# LARIX_V5_1.net
KiCad netlist of a schematic drawn in EAGLE
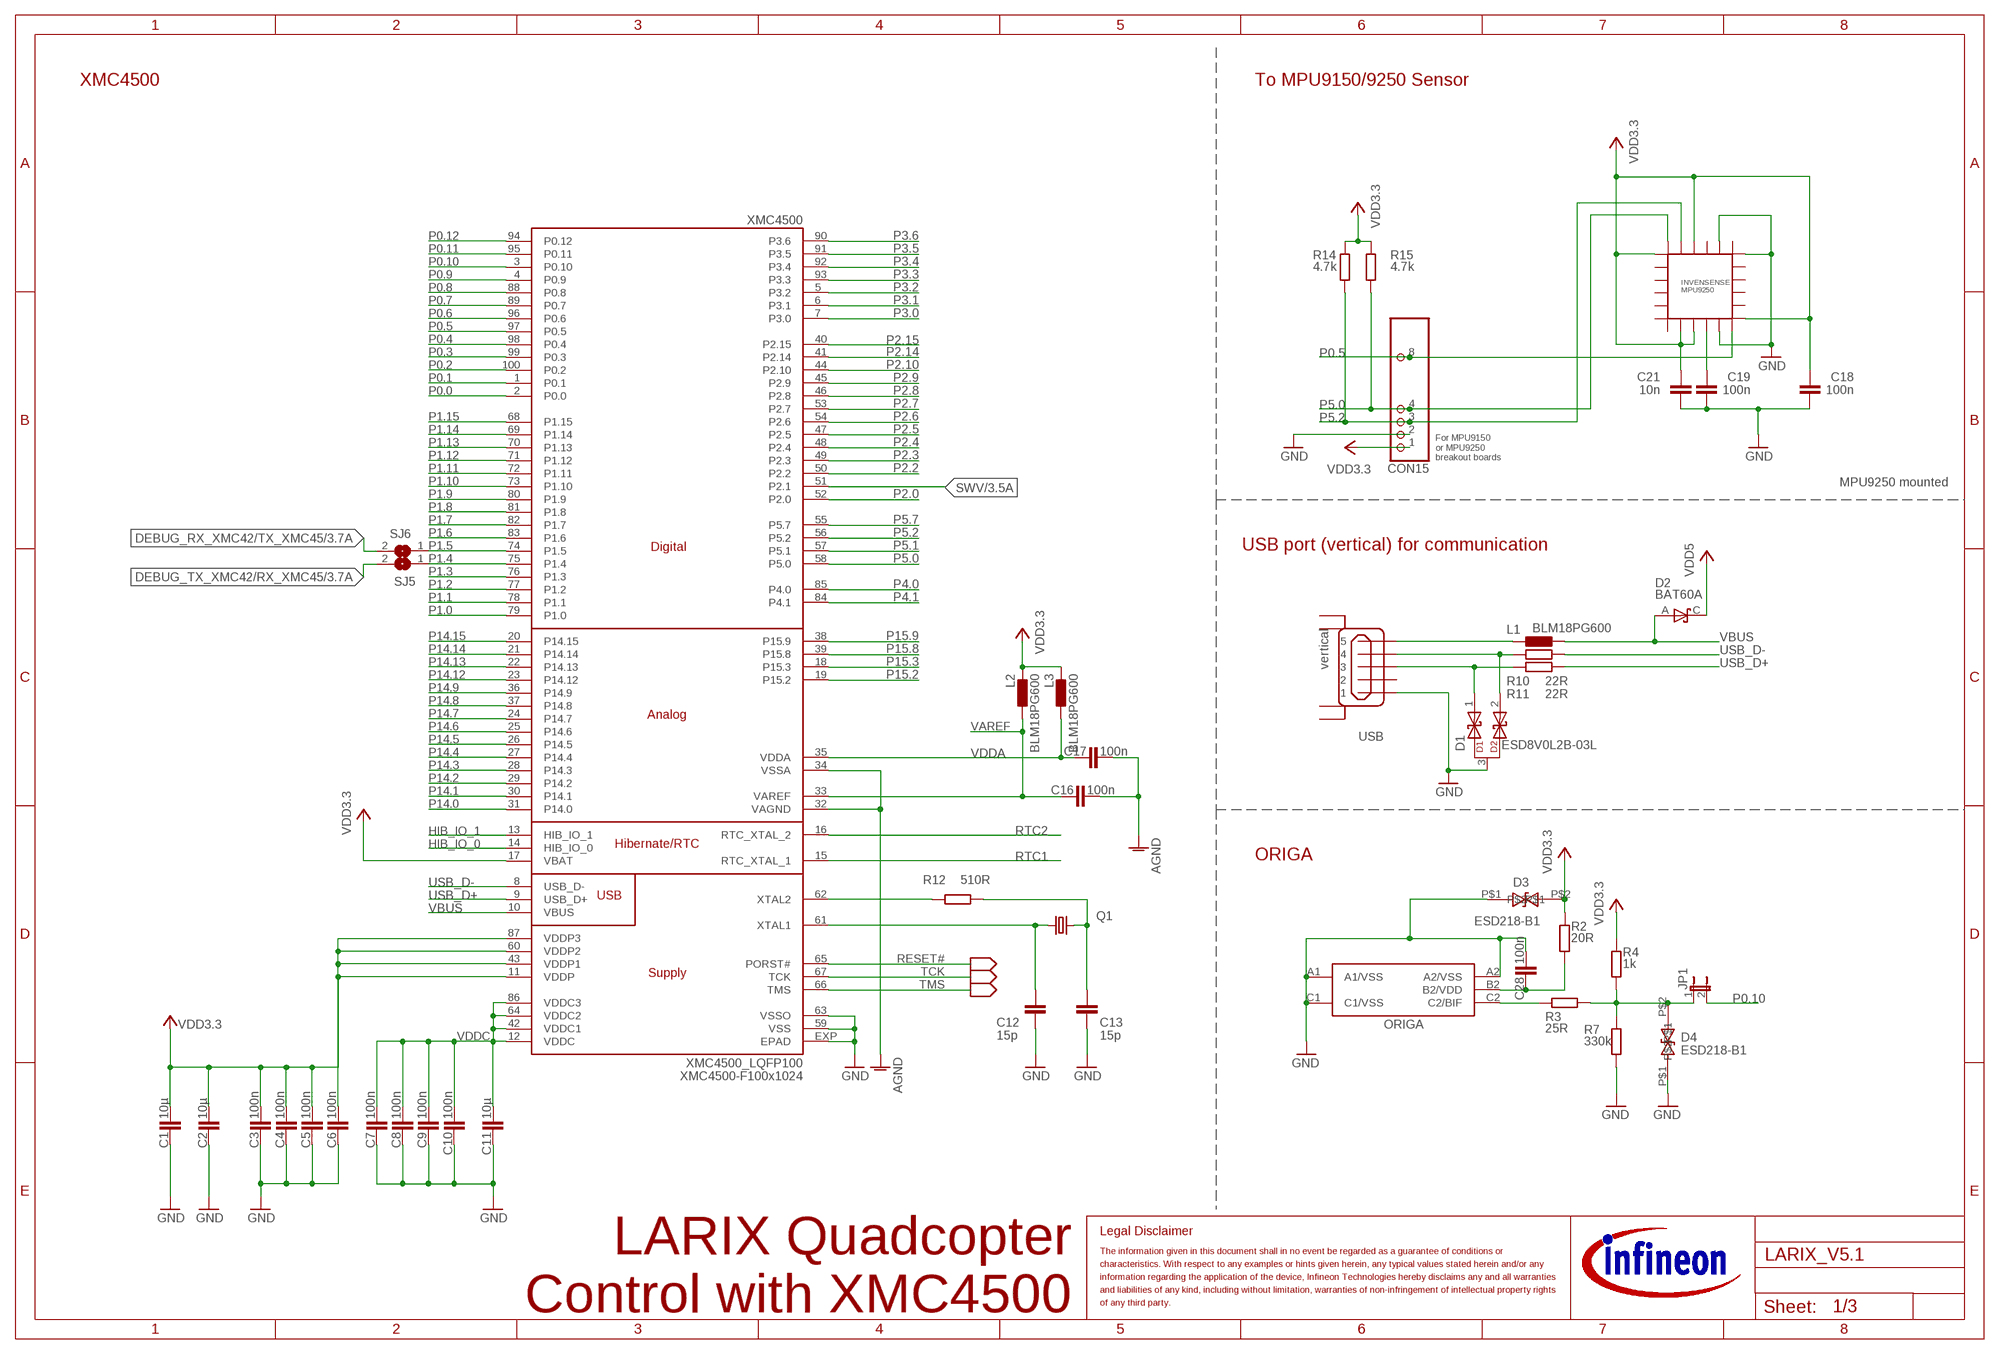
[diagram p0: schematic, sheet 1]
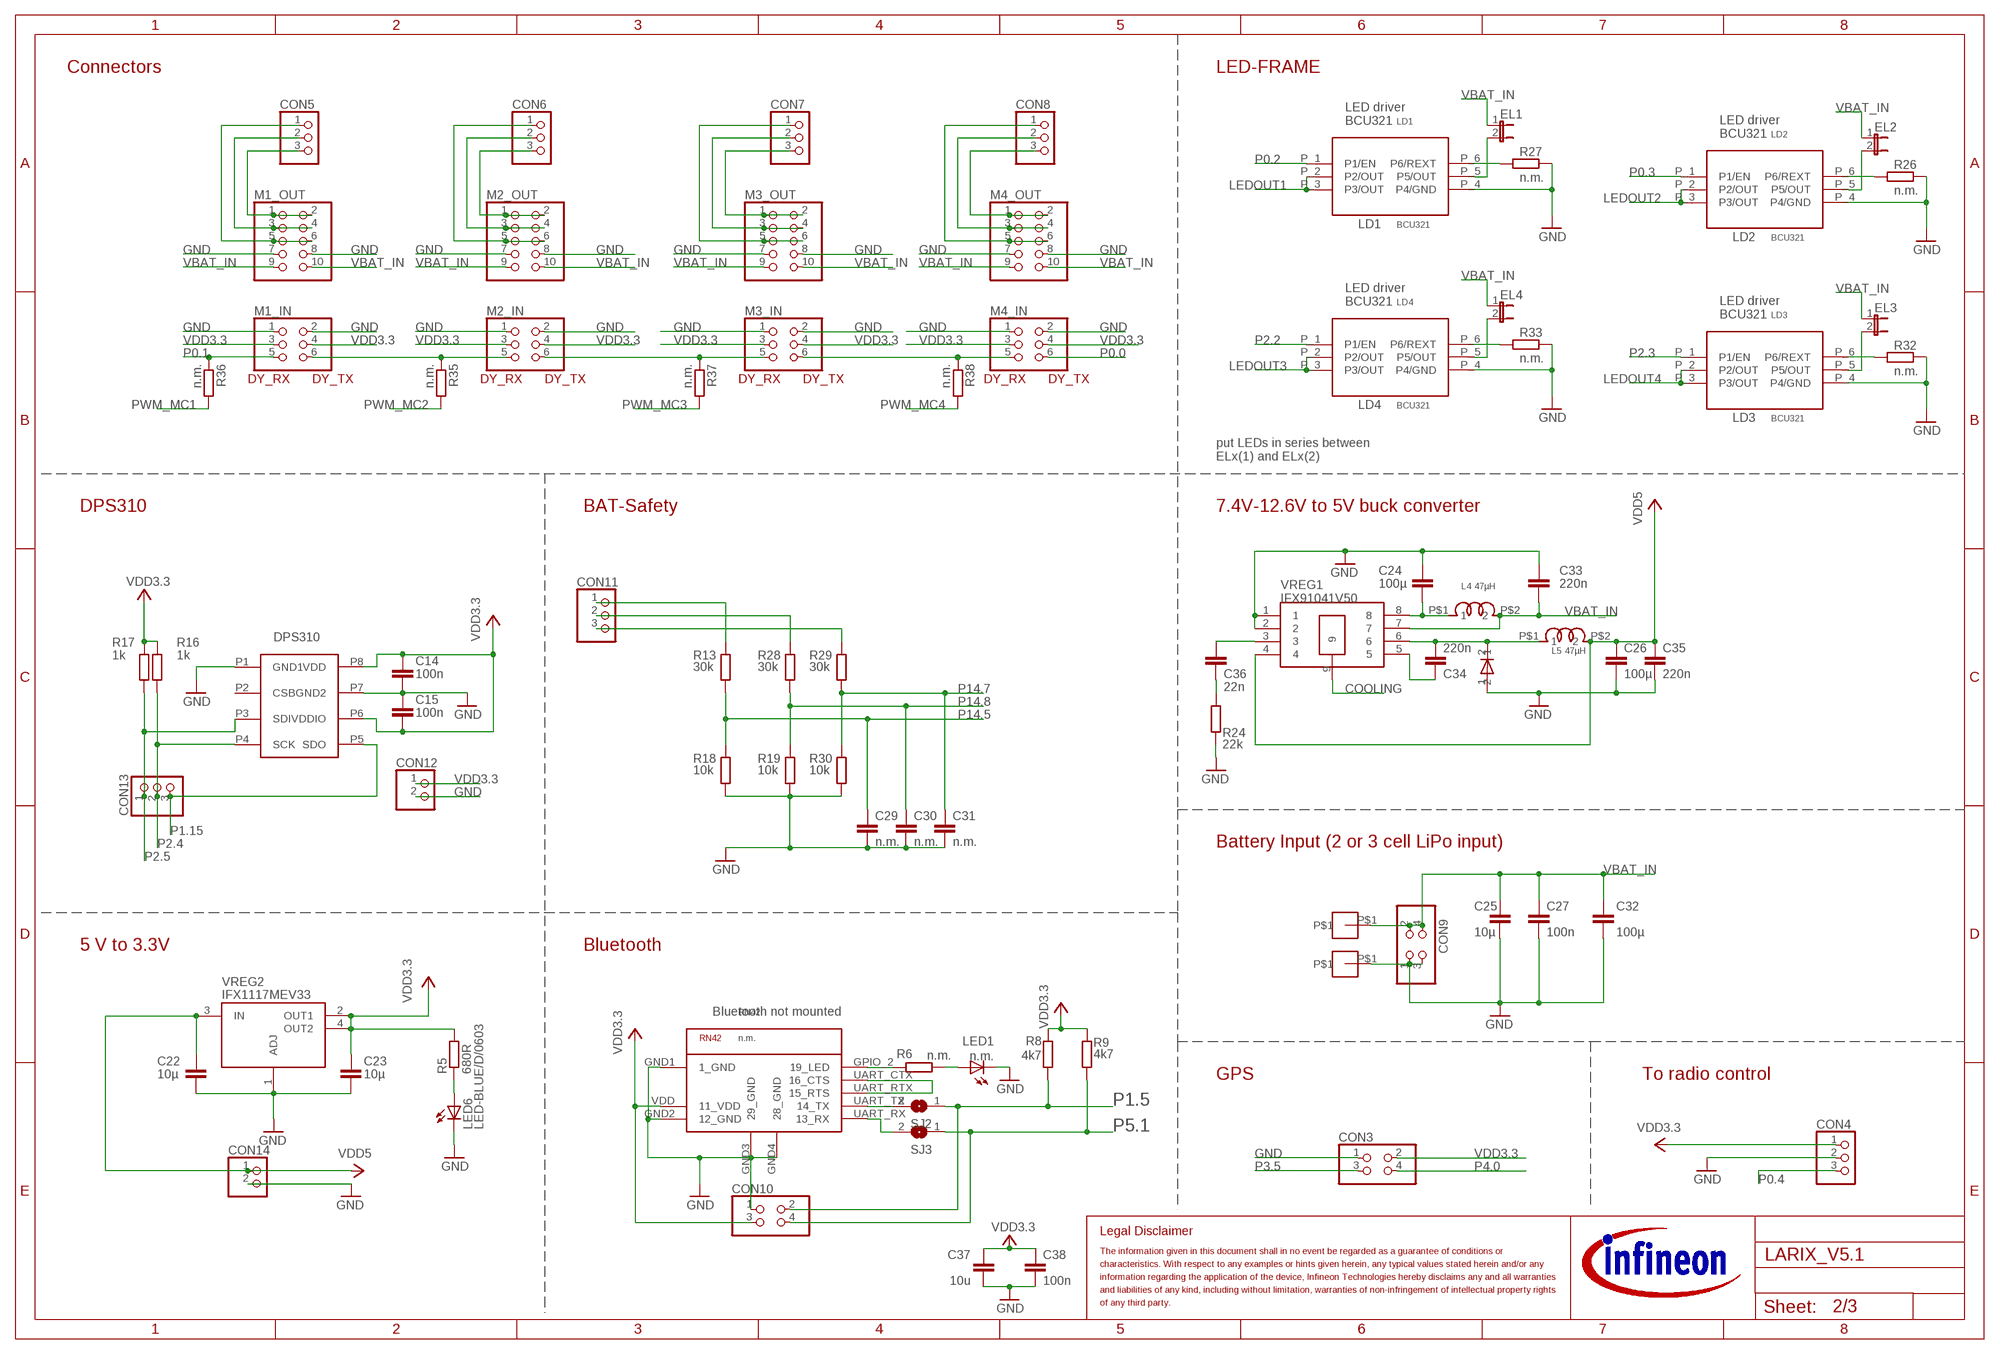
[diagram p1: schematic, sheet 2]
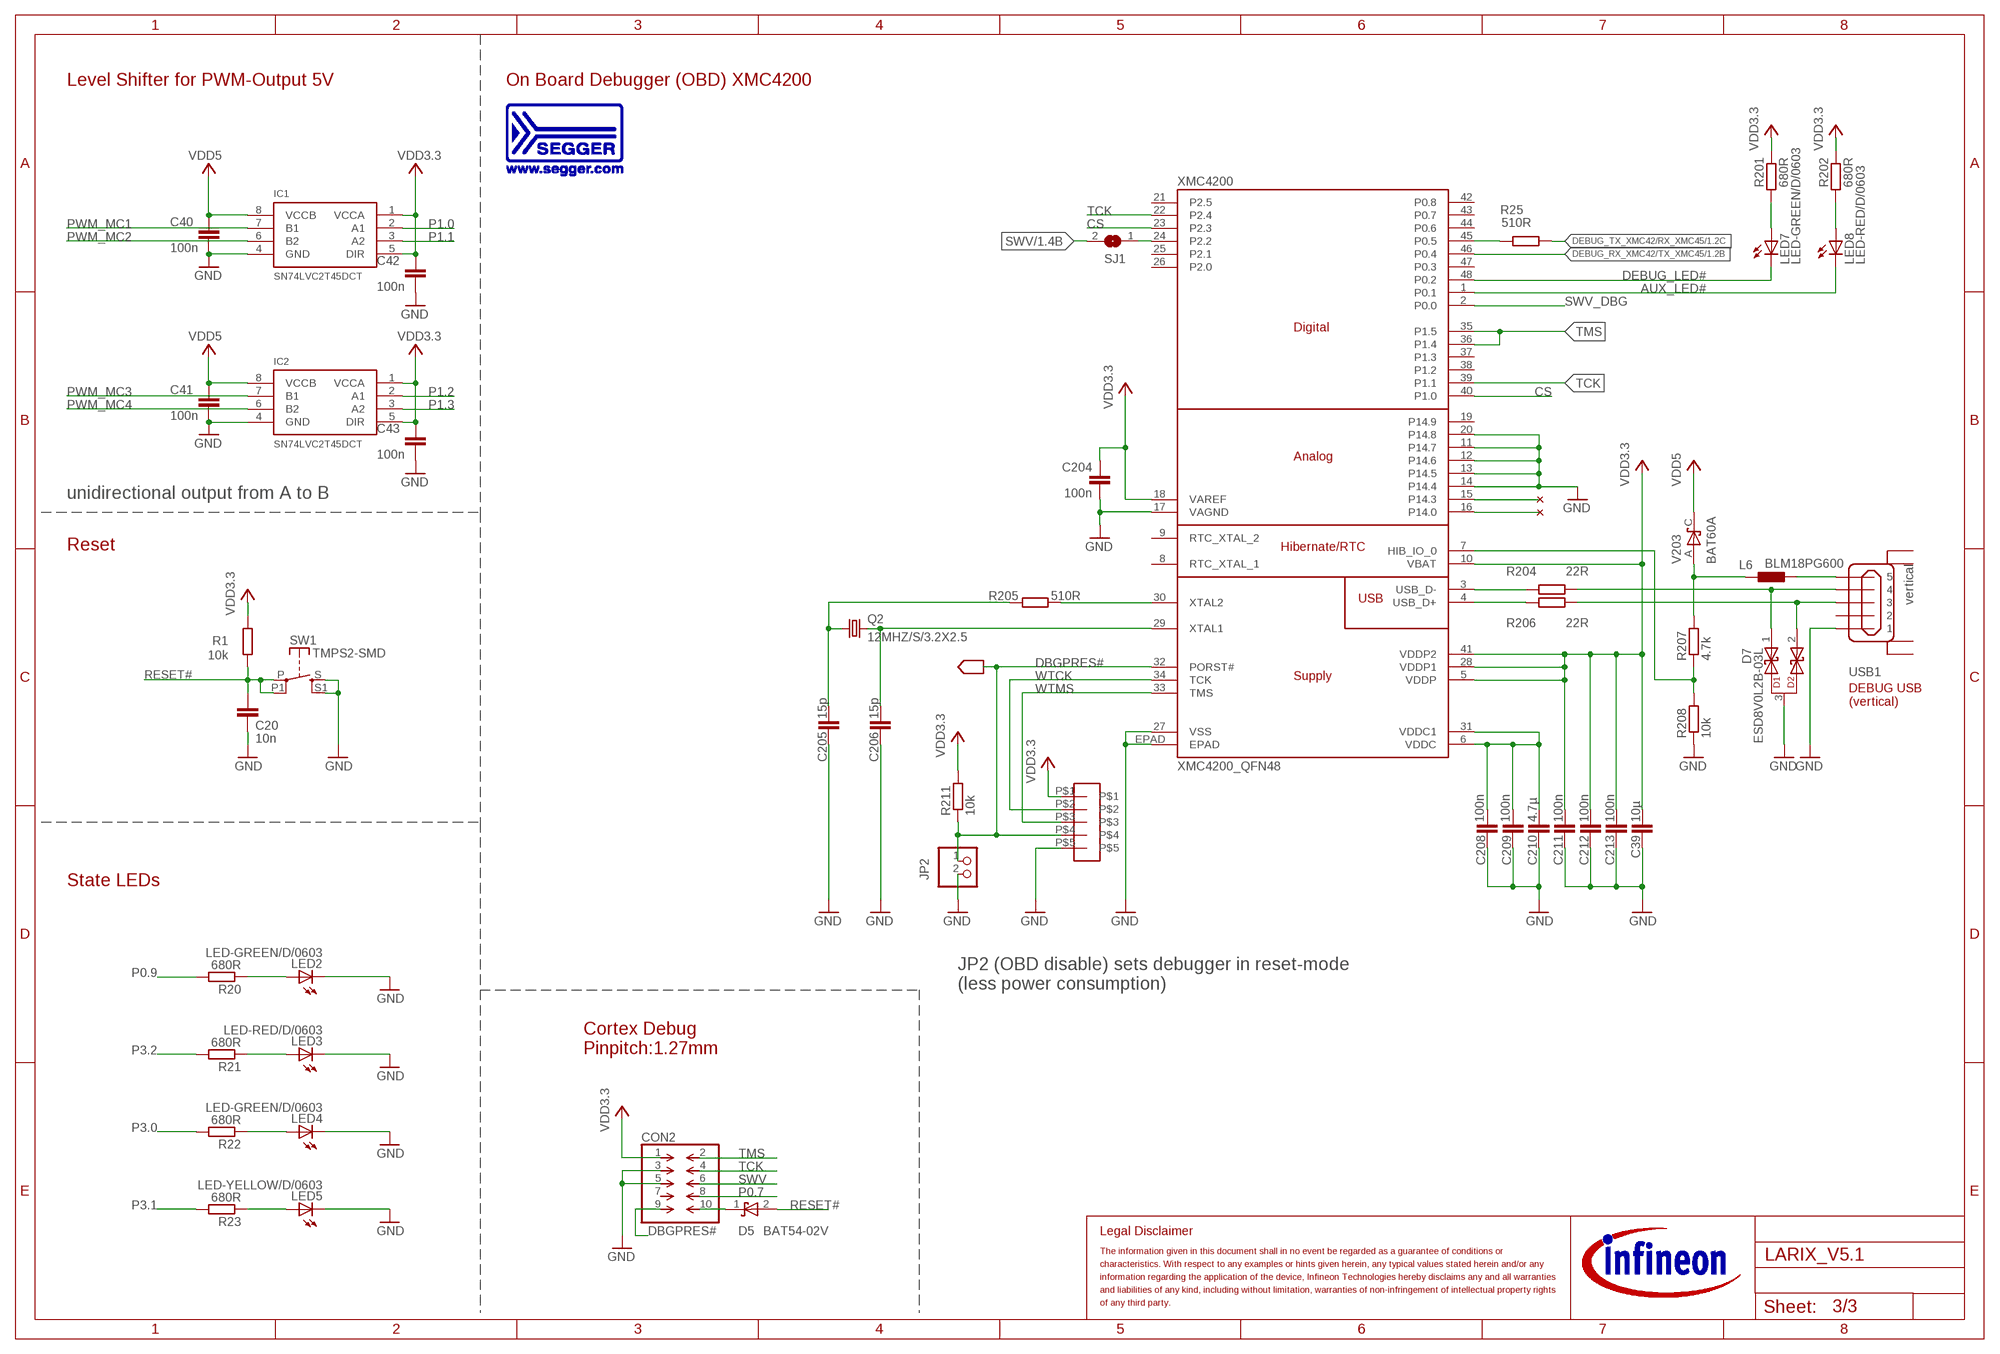
[diagram p2: schematic, sheet 3]

(export (version "E")
  (design (tool "Eeschema 10.0.6"))
  (components
    (comp (ref "C14")
      (value "100n")
      (footprint "eagle-import:C0603")
      (libsource (lib "eagle-import") (part "libresistor_C-EUC0603"))
    )
    (comp (ref "C15")
      (value "100n")
      (footprint "eagle-import:C0603")
      (libsource (lib "eagle-import") (part "libresistor_C-EUC0603"))
    )
    (comp (ref "C22")
      (value "10µ")
      (footprint "eagle-import:C0805K")
      (libsource (lib "eagle-import") (part "C-EUC0805K"))
    )
    (comp (ref "C23")
      (value "10µ")
      (footprint "eagle-import:C0805K")
      (libsource (lib "eagle-import") (part "C-EUC0805K"))
    )
    (comp (ref "C24")
      (value "100µ")
      (footprint "eagle-import:C1210")
      (libsource (lib "eagle-import") (part "libresistor_C-EUC1210"))
    )
    (comp (ref "C25")
      (value "10µ")
      (footprint "eagle-import:C0805K")
      (libsource (lib "eagle-import") (part "C-EUC0805K"))
    )
    (comp (ref "C26")
      (value "100µ")
      (footprint "eagle-import:C1210")
      (libsource (lib "eagle-import") (part "libresistor_C-EUC1210"))
    )
    (comp (ref "C27")
      (value "100n")
      (footprint "eagle-import:C0603")
      (libsource (lib "eagle-import") (part "libresistor_C-EUC0603"))
    )
    (comp (ref "C29")
      (value "n.m.")
      (footprint "eagle-import:C0603")
      (libsource (lib "eagle-import") (part "libresistor_C-EUC0603"))
    )
    (comp (ref "C30")
      (value "n.m.")
      (footprint "eagle-import:C0603")
      (libsource (lib "eagle-import") (part "libresistor_C-EUC0603"))
    )
    (comp (ref "C31")
      (value "n.m.")
      (footprint "eagle-import:C0603")
      (libsource (lib "eagle-import") (part "libresistor_C-EUC0603"))
    )
    (comp (ref "C32")
      (value "100µ")
      (footprint "eagle-import:C1210")
      (libsource (lib "eagle-import") (part "libresistor_C-EUC1210"))
    )
    (comp (ref "C33")
      (value "220n")
      (footprint "eagle-import:C0603")
      (libsource (lib "eagle-import") (part "libresistor_C-EUC0603"))
    )
    (comp (ref "C34")
      (value "220n")
      (footprint "eagle-import:C0603")
      (libsource (lib "eagle-import") (part "libresistor_C-EUC0603"))
    )
    (comp (ref "C35")
      (value "220n")
      (footprint "eagle-import:C0603")
      (libsource (lib "eagle-import") (part "libresistor_C-EUC0603"))
    )
    (comp (ref "C36")
      (value "22n")
      (footprint "eagle-import:C0603")
      (libsource (lib "eagle-import") (part "libresistor_C-EUC0603"))
    )
    (comp (ref "C37")
      (value "10u")
      (footprint "eagle-import:C0805K")
      (libsource (lib "eagle-import") (part "C-EUC0805K"))
    )
    (comp (ref "C38")
      (value "100n")
      (footprint "eagle-import:C0603")
      (libsource (lib "eagle-import") (part "libresistor_C-EUC0603"))
    )
    (comp (ref "CON3")
      (value "PINHD-2X2")
      (footprint "eagle-import:2X02")
      (libsource (lib "eagle-import") (part "PINHD-2X2"))
    )
    (comp (ref "CON4")
      (value "PINHD-1X3")
      (footprint "eagle-import:1X03")
      (libsource (lib "eagle-import") (part "PINHD-1X3"))
    )
    (comp (ref "CON5")
      (value "PINHD-1X3")
      (footprint "eagle-import:1X03")
      (libsource (lib "eagle-import") (part "PINHD-1X3"))
    )
    (comp (ref "CON6")
      (value "PINHD-1X3")
      (footprint "eagle-import:1X03")
      (libsource (lib "eagle-import") (part "PINHD-1X3"))
    )
    (comp (ref "CON7")
      (value "PINHD-1X3")
      (footprint "eagle-import:1X03")
      (libsource (lib "eagle-import") (part "PINHD-1X3"))
    )
    (comp (ref "CON8")
      (value "PINHD-1X3")
      (footprint "eagle-import:1X03")
      (libsource (lib "eagle-import") (part "PINHD-1X3"))
    )
    (comp (ref "CON9")
      (value "PINHD-2X2")
      (footprint "eagle-import:2X02")
      (libsource (lib "eagle-import") (part "PINHD-2X2"))
    )
    (comp (ref "CON10")
      (value "PINHD-2X2")
      (footprint "eagle-import:2X02")
      (libsource (lib "eagle-import") (part "PINHD-2X2"))
    )
    (comp (ref "CON11")
      (value "PINHD-1X3")
      (footprint "eagle-import:1X03")
      (libsource (lib "eagle-import") (part "PINHD-1X3"))
    )
    (comp (ref "CON12")
      (value "PINHD-1X2")
      (footprint "eagle-import:1X02")
      (libsource (lib "eagle-import") (part "PINHD-1X2"))
    )
    (comp (ref "CON13")
      (value "PINHD-1X3")
      (footprint "eagle-import:1X03")
      (libsource (lib "eagle-import") (part "PINHD-1X3"))
    )
    (comp (ref "CON14")
      (value "PINHD-1X2")
      (footprint "eagle-import:1X02")
      (libsource (lib "eagle-import") (part "PINHD-1X2"))
    )
    (comp (ref "D6")
      (value "BAS21-03W")
      (footprint "eagle-import:INF-SOD323_V_1PRIMARY")
      (libsource (lib "eagle-import") (part "INF-SOD323_V_1"))
    )
    (comp (ref "DPS310")
      (value "Infineon")
      (footprint "eagle-import:LGA8R125P0X4_500X300X120")
      (libsource (lib "eagle-import") (part "DPS310DRUCKSENSOR"))
    )
    (comp (ref "EL1")
      (value "JP1E")
      (footprint "eagle-import:JP1")
      (libsource (lib "eagle-import") (part "libjumper_JP1E"))
    )
    (comp (ref "EL2")
      (value "JP1E")
      (footprint "eagle-import:JP1")
      (libsource (lib "eagle-import") (part "libjumper_JP1E"))
    )
    (comp (ref "EL3")
      (value "JP1E")
      (footprint "eagle-import:JP1")
      (libsource (lib "eagle-import") (part "libjumper_JP1E"))
    )
    (comp (ref "EL4")
      (value "JP1E")
      (footprint "eagle-import:JP1")
      (libsource (lib "eagle-import") (part "libjumper_JP1E"))
    )
    (comp (ref "L4")
      (value "47µH")
      (footprint "eagle-import:WE-TPC")
      (libsource (lib "eagle-import") (part "WUERTH47UHIND"))
    )
    (comp (ref "L5")
      (value "47µH")
      (footprint "eagle-import:WE-TPC")
      (libsource (lib "eagle-import") (part "WUERTH47UHIND"))
    )
    (comp (ref "LD1")
      (value "BCU321")
      (footprint "eagle-import:SC74")
      (libsource (lib "eagle-import") (part "BCU320"))
    )
    (comp (ref "LD2")
      (value "BCU321")
      (footprint "eagle-import:SC74")
      (libsource (lib "eagle-import") (part "BCU320"))
    )
    (comp (ref "LD3")
      (value "BCU321")
      (footprint "eagle-import:SC74")
      (libsource (lib "eagle-import") (part "BCU320"))
    )
    (comp (ref "LD4")
      (value "BCU321")
      (footprint "eagle-import:SC74")
      (libsource (lib "eagle-import") (part "BCU320"))
    )
    (comp (ref "LED1")
      (value "n.m.")
      (footprint "eagle-import:CHIPLED_0603")
      (libsource (lib "eagle-import") (part "LEDCHIPLED_0603"))
    )
    (comp (ref "LED6")
      (value "LED-BLUE/D/0603")
      (footprint "eagle-import:CHIPLED_0603")
      (libsource (lib "eagle-import") (part "LEDCHIPLED_0603"))
    )
    (comp (ref "M1_IN")
      (value "PINHD-2X3")
      (footprint "eagle-import:2X03")
      (libsource (lib "eagle-import") (part "PINHD-2X3"))
    )
    (comp (ref "M1_OUT")
      (value "PINHD-2X5")
      (footprint "eagle-import:2X05")
      (libsource (lib "eagle-import") (part "PINHD-2X5"))
    )
    (comp (ref "M2_IN")
      (value "PINHD-2X3")
      (footprint "eagle-import:2X03")
      (libsource (lib "eagle-import") (part "PINHD-2X3"))
    )
    (comp (ref "M2_OUT")
      (value "PINHD-2X5")
      (footprint "eagle-import:2X05")
      (libsource (lib "eagle-import") (part "PINHD-2X5"))
    )
    (comp (ref "M3_IN")
      (value "PINHD-2X3")
      (footprint "eagle-import:2X03")
      (libsource (lib "eagle-import") (part "PINHD-2X3"))
    )
    (comp (ref "M3_OUT")
      (value "PINHD-2X5")
      (footprint "eagle-import:2X05")
      (libsource (lib "eagle-import") (part "PINHD-2X5"))
    )
    (comp (ref "M4_IN")
      (value "PINHD-2X3")
      (footprint "eagle-import:2X03")
      (libsource (lib "eagle-import") (part "PINHD-2X3"))
    )
    (comp (ref "M4_OUT")
      (value "PINHD-2X5")
      (footprint "eagle-import:2X05")
      (libsource (lib "eagle-import") (part "PINHD-2X5"))
    )
    (comp (ref "PAD1")
      (value "PAD-BATTERY")
      (footprint "eagle-import:BATT-SOLDER")
      (libsource (lib "eagle-import") (part "PAD-BATTERY"))
    )
    (comp (ref "PAD2")
      (value "PAD-BATTERY")
      (footprint "eagle-import:BATT-SOLDER")
      (libsource (lib "eagle-import") (part "PAD-BATTERY"))
    )
    (comp (ref "R5")
      (value "680R")
      (footprint "eagle-import:R0603")
      (libsource (lib "eagle-import") (part "R-EU_R0603"))
    )
    (comp (ref "R6")
      (value "n.m.")
      (footprint "eagle-import:R0603")
      (libsource (lib "eagle-import") (part "R-EU_R0603"))
    )
    (comp (ref "R8")
      (value "4k7")
      (footprint "eagle-import:R0603")
      (libsource (lib "eagle-import") (part "R-EU_R0603"))
    )
    (comp (ref "R9")
      (value "4k7")
      (footprint "eagle-import:R0603")
      (libsource (lib "eagle-import") (part "R-EU_R0603"))
    )
    (comp (ref "R13")
      (value "30k")
      (footprint "eagle-import:R0603")
      (libsource (lib "eagle-import") (part "R-EU_R0603"))
    )
    (comp (ref "R16")
      (value "1k")
      (footprint "eagle-import:R0603")
      (libsource (lib "eagle-import") (part "R-EU_R0603"))
    )
    (comp (ref "R17")
      (value "1k")
      (footprint "eagle-import:R0603")
      (libsource (lib "eagle-import") (part "R-EU_R0603"))
    )
    (comp (ref "R18")
      (value "10k")
      (footprint "eagle-import:R0603")
      (libsource (lib "eagle-import") (part "R-EU_R0603"))
    )
    (comp (ref "R19")
      (value "10k")
      (footprint "eagle-import:R0603")
      (libsource (lib "eagle-import") (part "R-EU_R0603"))
    )
    (comp (ref "R24")
      (value "22k")
      (footprint "eagle-import:R0603")
      (libsource (lib "eagle-import") (part "R-EU_R0603"))
    )
    (comp (ref "R26")
      (value "n.m.")
      (footprint "eagle-import:R0603")
      (libsource (lib "eagle-import") (part "libresistor_R-EU_R0603"))
    )
    (comp (ref "R27")
      (value "n.m.")
      (footprint "eagle-import:R0603")
      (libsource (lib "eagle-import") (part "libresistor_R-EU_R0603"))
    )
    (comp (ref "R28")
      (value "30k")
      (footprint "eagle-import:R0603")
      (libsource (lib "eagle-import") (part "R-EU_R0603"))
    )
    (comp (ref "R29")
      (value "30k")
      (footprint "eagle-import:R0603")
      (libsource (lib "eagle-import") (part "R-EU_R0603"))
    )
    (comp (ref "R30")
      (value "10k")
      (footprint "eagle-import:R0603")
      (libsource (lib "eagle-import") (part "R-EU_R0603"))
    )
    (comp (ref "R32")
      (value "n.m.")
      (footprint "eagle-import:R0603")
      (libsource (lib "eagle-import") (part "libresistor_R-EU_R0603"))
    )
    (comp (ref "R33")
      (value "n.m.")
      (footprint "eagle-import:R0603")
      (libsource (lib "eagle-import") (part "libresistor_R-EU_R0603"))
    )
    (comp (ref "R35")
      (value "n.m.")
      (footprint "eagle-import:R0603")
      (libsource (lib "eagle-import") (part "libresistor_R-EU_R0603"))
    )
    (comp (ref "R36")
      (value "n.m.")
      (footprint "eagle-import:R0603")
      (libsource (lib "eagle-import") (part "libresistor_R-EU_R0603"))
    )
    (comp (ref "R37")
      (value "n.m.")
      (footprint "eagle-import:R0603")
      (libsource (lib "eagle-import") (part "R-EU_R0603"))
    )
    (comp (ref "R38")
      (value "n.m.")
      (footprint "eagle-import:R0603")
      (libsource (lib "eagle-import") (part "libresistor_R-EU_R0603"))
    )
    (comp (ref "RN42")
      (value "n.m.")
      (footprint "eagle-import:RN42+SHIELD")
      (libsource (lib "eagle-import") (part "BLUETOOTHRN42+SHIELD"))
    )
    (comp (ref "SJ2") (value "SJ") (footprint "eagle-import:SJ") (libsource (lib "eagle-import") (part "SJ")))
    (comp (ref "SJ3") (value "SJ") (footprint "eagle-import:SJ") (libsource (lib "eagle-import") (part "SJ")))
    (comp (ref "VREG1")
      (value "IFX91041V50")
      (footprint "eagle-import:INF-PG-DSO-8-27_N_1PRIMARY")
      (libsource (lib "eagle-import") (part "INF-PG-DSO-8-27_N_1"))
    )
    (comp (ref "VREG2")
      (value "IFX1117MEV33")
      (footprint "eagle-import:SOT223")
      (libsource (lib "eagle-import") (part "IFX1117"))
    )
    (comp (ref "C1")
      (value "10µ")
      (footprint "eagle-import:C0805K")
      (libsource (lib "eagle-import") (part "C-EUC0805K"))
    )
    (comp (ref "C2")
      (value "10µ")
      (footprint "eagle-import:C0805K")
      (libsource (lib "eagle-import") (part "C-EUC0805K"))
    )
    (comp (ref "C3")
      (value "100n")
      (footprint "eagle-import:C0603")
      (libsource (lib "eagle-import") (part "libresistor_C-EUC0603"))
    )
    (comp (ref "C4")
      (value "100n")
      (footprint "eagle-import:C0603")
      (libsource (lib "eagle-import") (part "libresistor_C-EUC0603"))
    )
    (comp (ref "C5")
      (value "100n")
      (footprint "eagle-import:C0603")
      (libsource (lib "eagle-import") (part "libresistor_C-EUC0603"))
    )
    (comp (ref "C6")
      (value "100n")
      (footprint "eagle-import:C0603")
      (libsource (lib "eagle-import") (part "libresistor_C-EUC0603"))
    )
    (comp (ref "C7")
      (value "100n")
      (footprint "eagle-import:C0603")
      (libsource (lib "eagle-import") (part "libresistor_C-EUC0603"))
    )
    (comp (ref "C8")
      (value "100n")
      (footprint "eagle-import:C0603")
      (libsource (lib "eagle-import") (part "libresistor_C-EUC0603"))
    )
    (comp (ref "C9")
      (value "100n")
      (footprint "eagle-import:C0603")
      (libsource (lib "eagle-import") (part "libresistor_C-EUC0603"))
    )
    (comp (ref "C10")
      (value "100n")
      (footprint "eagle-import:C0603")
      (libsource (lib "eagle-import") (part "libresistor_C-EUC0603"))
    )
    (comp (ref "C11")
      (value "10µ")
      (footprint "eagle-import:C0805K")
      (libsource (lib "eagle-import") (part "C-EUC0805K"))
    )
    (comp (ref "C12")
      (value "15p")
      (footprint "eagle-import:C0603")
      (libsource (lib "eagle-import") (part "libresistor_C-EUC0603"))
    )
    (comp (ref "C13")
      (value "15p")
      (footprint "eagle-import:C0603")
      (libsource (lib "eagle-import") (part "libresistor_C-EUC0603"))
    )
    (comp (ref "C16")
      (value "100n")
      (footprint "eagle-import:C0603")
      (libsource (lib "eagle-import") (part "libresistor_C-EUC0603"))
    )
    (comp (ref "C17")
      (value "100n")
      (footprint "eagle-import:C0603")
      (libsource (lib "eagle-import") (part "libresistor_C-EUC0603"))
    )
    (comp (ref "C18")
      (value "100n")
      (footprint "eagle-import:C0603")
      (libsource (lib "eagle-import") (part "libresistor_C-EUC0603"))
    )
    (comp (ref "C19")
      (value "100n")
      (footprint "eagle-import:C0603")
      (libsource (lib "eagle-import") (part "libresistor_C-EUC0603"))
    )
    (comp (ref "C21")
      (value "10n")
      (footprint "eagle-import:C0603")
      (libsource (lib "eagle-import") (part "libresistor_C-EUC0603"))
    )
    (comp (ref "C28")
      (value "100n")
      (footprint "eagle-import:C0603")
      (libsource (lib "eagle-import") (part "libresistor_C-EUC0603"))
    )
    (comp (ref "CON15")
      (value "PINHD-1X10")
      (footprint "eagle-import:1X10")
      (libsource (lib "eagle-import") (part "PINHD-1X10"))
    )
    (comp (ref "D1")
      (value "ESD8V0L2B-03L")
      (footprint "eagle-import:TSLP-3-1")
      (libsource (lib "eagle-import") (part "ESD8V0L2B-03L"))
    )
    (comp (ref "D2")
      (value "BAT60A")
      (footprint "eagle-import:SOD323-R")
      (libsource (lib "eagle-import") (part "BAT60"))
    )
    (comp (ref "D3")
      (value "ESD218-B1-02EL")
      (footprint "eagle-import:TSLP-2-20")
      (libsource (lib "eagle-import") (part "ESD218-B1-02EL"))
    )
    (comp (ref "D4")
      (value "ESD218-B1-02EL")
      (footprint "eagle-import:TSLP-2-20")
      (libsource (lib "eagle-import") (part "ESD218-B1-02EL"))
    )
    (comp (ref "JP1")
      (value "JP1E")
      (footprint "eagle-import:JP1")
      (libsource (lib "eagle-import") (part "JP1E"))
    )
    (comp (ref "L1")
      (value "BLM18PG600")
      (footprint "eagle-import:L1608")
      (libsource (lib "eagle-import") (part "L_EU_L0603"))
    )
    (comp (ref "L2")
      (value "BLM18PG600")
      (footprint "eagle-import:L1608")
      (libsource (lib "eagle-import") (part "L_EU_L0603"))
    )
    (comp (ref "L3")
      (value "BLM18PG600")
      (footprint "eagle-import:L1608")
      (libsource (lib "eagle-import") (part "L_EU_L0603"))
    )
    (comp (ref "MPU9250")
      (value "MPU9250")
      (footprint "eagle-import:QFN3X3-24+")
      (libsource (lib "eagle-import") (part "INVENSENSE9250HERBYE"))
    )
    (comp (ref "ORIGA")
      (value "ORIGA2L")
      (footprint "eagle-import:WLB-5")
      (libsource (lib "eagle-import") (part "ORIGA2L"))
    )
    (comp (ref "Q1")
      (value "12MHZ/S/3.2X2.5")
      (footprint "eagle-import:32X25_4PAD")
      (libsource (lib "eagle-import") (part "NX3225_2"))
    )
    (comp (ref "R2")
      (value "20R")
      (footprint "eagle-import:R0603")
      (libsource (lib "eagle-import") (part "R-EU_R0603"))
    )
    (comp (ref "R3")
      (value "25R")
      (footprint "eagle-import:R0603")
      (libsource (lib "eagle-import") (part "R-EU_R0603"))
    )
    (comp (ref "R4")
      (value "1k")
      (footprint "eagle-import:R0603")
      (libsource (lib "eagle-import") (part "R-EU_R0603"))
    )
    (comp (ref "R7")
      (value "330k")
      (footprint "eagle-import:R0603")
      (libsource (lib "eagle-import") (part "R-EU_R0603"))
    )
    (comp (ref "R10")
      (value "22R")
      (footprint "eagle-import:R0603")
      (libsource (lib "eagle-import") (part "libresistor_R-EU_R0603"))
    )
    (comp (ref "R11")
      (value "22R")
      (footprint "eagle-import:R0603")
      (libsource (lib "eagle-import") (part "libresistor_R-EU_R0603"))
    )
    (comp (ref "R12")
      (value "510R")
      (footprint "eagle-import:R0603")
      (libsource (lib "eagle-import") (part "R-EU_R0603"))
    )
    (comp (ref "R14")
      (value "4.7k")
      (footprint "eagle-import:R0603")
      (libsource (lib "eagle-import") (part "libresistor_R-EU_R0603"))
    )
    (comp (ref "R15")
      (value "4.7k")
      (footprint "eagle-import:R0603")
      (libsource (lib "eagle-import") (part "libresistor_R-EU_R0603"))
    )
    (comp (ref "SJ5") (value "SJ") (footprint "eagle-import:SJ") (libsource (lib "eagle-import") (part "SJ")))
    (comp (ref "SJ6") (value "SJ") (footprint "eagle-import:SJ") (libsource (lib "eagle-import") (part "SJ")))
    (comp (ref "USB")
      (value "vertical")
      (footprint "eagle-import:USBVERTICAL")
      (libsource (lib "eagle-import") (part "MICRO_USB_VERTICAL"))
    )
    (comp (ref "XMC4500")
      (value "XMC4500_LQFP100")
      (footprint "eagle-import:P_PG-LQFP-100-11")
      (libsource (lib "eagle-import") (part "XMC4400_LQFP100"))
    )
    (comp (ref "C20")
      (value "10n")
      (footprint "eagle-import:C0603")
      (libsource (lib "eagle-import") (part "libresistor_C-EUC0603"))
    )
    (comp (ref "C39")
      (value "10µ")
      (footprint "eagle-import:C0805K")
      (libsource (lib "eagle-import") (part "C-EUC0805K"))
    )
    (comp (ref "C40")
      (value "100n")
      (footprint "eagle-import:C0603")
      (libsource (lib "eagle-import") (part "libresistor_C-EUC0603"))
    )
    (comp (ref "C41")
      (value "100n")
      (footprint "eagle-import:C0603")
      (libsource (lib "eagle-import") (part "libresistor_C-EUC0603"))
    )
    (comp (ref "C42")
      (value "100n")
      (footprint "eagle-import:C0603")
      (libsource (lib "eagle-import") (part "libresistor_C-EUC0603"))
    )
    (comp (ref "C43")
      (value "100n")
      (footprint "eagle-import:C0603")
      (libsource (lib "eagle-import") (part "libresistor_C-EUC0603"))
    )
    (comp (ref "C204")
      (value "100n")
      (footprint "eagle-import:C0402")
      (libsource (lib "eagle-import") (part "C-EUC0402"))
    )
    (comp (ref "C205")
      (value "15p")
      (footprint "eagle-import:C0402")
      (libsource (lib "eagle-import") (part "C-EUC0402"))
    )
    (comp (ref "C206")
      (value "15p")
      (footprint "eagle-import:C0402")
      (libsource (lib "eagle-import") (part "C-EUC0402"))
    )
    (comp (ref "C208")
      (value "100n")
      (footprint "eagle-import:C0402")
      (libsource (lib "eagle-import") (part "C-EUC0402"))
    )
    (comp (ref "C209")
      (value "100n")
      (footprint "eagle-import:C0402")
      (libsource (lib "eagle-import") (part "C-EUC0402"))
    )
    (comp (ref "C210")
      (value "4.7µ")
      (footprint "eagle-import:C0805K")
      (libsource (lib "eagle-import") (part "C-EUC0805K"))
    )
    (comp (ref "C211")
      (value "100n")
      (footprint "eagle-import:C0402")
      (libsource (lib "eagle-import") (part "C-EUC0402"))
    )
    (comp (ref "C212")
      (value "100n")
      (footprint "eagle-import:C0402")
      (libsource (lib "eagle-import") (part "C-EUC0402"))
    )
    (comp (ref "C213")
      (value "100n")
      (footprint "eagle-import:C0402")
      (libsource (lib "eagle-import") (part "C-EUC0402"))
    )
    (comp (ref "CON2")
      (value "FTSH-105-01-F-D-K")
      (footprint "eagle-import:FTSH-105-01-F-D-K")
      (libsource (lib "eagle-import") (part "FTSH-105-01-F-D-K"))
    )
    (comp (ref "D5")
      (value "BAT54-02V")
      (footprint "eagle-import:SC79")
      (libsource (lib "eagle-import") (part "BAT54-02V"))
    )
    (comp (ref "D7")
      (value "ESD8V0L2B-03L")
      (footprint "eagle-import:TSLP-3-1")
      (libsource (lib "eagle-import") (part "ESD8V0L2B-03L"))
    )
    (comp (ref "IC1")
      (value "SN74LVC2T45DCT")
      (footprint "eagle-import:DCT_R-PDSO-G8")
      (libsource (lib "eagle-import") (part "SN74LVC2T45DCT"))
    )
    (comp (ref "IC2")
      (value "SN74LVC2T45DCT")
      (footprint "eagle-import:DCT_R-PDSO-G8")
      (libsource (lib "eagle-import") (part "SN74LVC2T45DCT"))
    )
    (comp (ref "JP2")
      (value "PINHD-1X2")
      (footprint "eagle-import:1X02")
      (libsource (lib "eagle-import") (part "PINHD-1X2"))
    )
    (comp (ref "L6")
      (value "BLM18PG600")
      (footprint "eagle-import:L1608")
      (libsource (lib "eagle-import") (part "L_EU_L0603"))
    )
    (comp (ref "LED2")
      (value "LED-GREEN/D/0603")
      (footprint "eagle-import:CHIPLED_0603")
      (libsource (lib "eagle-import") (part "LEDCHIPLED_0603"))
    )
    (comp (ref "LED3")
      (value "LED-RED/D/0603")
      (footprint "eagle-import:CHIPLED_0603")
      (libsource (lib "eagle-import") (part "LEDCHIPLED_0603"))
    )
    (comp (ref "LED4")
      (value "LED-GREEN/D/0603")
      (footprint "eagle-import:CHIPLED_0603")
      (libsource (lib "eagle-import") (part "LEDCHIPLED_0603"))
    )
    (comp (ref "LED5")
      (value "LED-YELLOW/D/0603")
      (footprint "eagle-import:CHIPLED_0603")
      (libsource (lib "eagle-import") (part "LEDCHIPLED_0603"))
    )
    (comp (ref "LED7")
      (value "LED-GREEN/D/0603")
      (footprint "eagle-import:CHIPLED_0603")
      (libsource (lib "eagle-import") (part "LEDCHIPLED_0603"))
    )
    (comp (ref "LED8")
      (value "LED-RED/D/0603")
      (footprint "eagle-import:CHIPLED_0603")
      (libsource (lib "eagle-import") (part "LEDCHIPLED_0603"))
    )
    (comp (ref "Q2")
      (value "12MHZ/S/3.2X2.5")
      (footprint "eagle-import:32X25_4PAD")
      (libsource (lib "eagle-import") (part "libXMC4700_Relax-V1_NX3225_2"))
    )
    (comp (ref "R1")
      (value "10k")
      (footprint "eagle-import:R0603")
      (libsource (lib "eagle-import") (part "libresistor_R-EU_R0603"))
    )
    (comp (ref "R20")
      (value "680R")
      (footprint "eagle-import:R0603")
      (libsource (lib "eagle-import") (part "R-EU_R0603"))
    )
    (comp (ref "R21")
      (value "680R")
      (footprint "eagle-import:R0603")
      (libsource (lib "eagle-import") (part "R-EU_R0603"))
    )
    (comp (ref "R22")
      (value "680R")
      (footprint "eagle-import:R0603")
      (libsource (lib "eagle-import") (part "R-EU_R0603"))
    )
    (comp (ref "R23")
      (value "680R")
      (footprint "eagle-import:R0603")
      (libsource (lib "eagle-import") (part "R-EU_R0603"))
    )
    (comp (ref "R25")
      (value "510R")
      (footprint "eagle-import:R0402")
      (libsource (lib "eagle-import") (part "R-EU_R0402"))
    )
    (comp (ref "R201")
      (value "680R")
      (footprint "eagle-import:R0603")
      (libsource (lib "eagle-import") (part "R-EU_R0603"))
    )
    (comp (ref "R202")
      (value "680R")
      (footprint "eagle-import:R0603")
      (libsource (lib "eagle-import") (part "R-EU_R0603"))
    )
    (comp (ref "R204")
      (value "22R")
      (footprint "eagle-import:R0402")
      (libsource (lib "eagle-import") (part "R-EU_R0402"))
    )
    (comp (ref "R205")
      (value "510R")
      (footprint "eagle-import:R0603")
      (libsource (lib "eagle-import") (part "R-EU_R0603"))
    )
    (comp (ref "R206")
      (value "22R")
      (footprint "eagle-import:R0402")
      (libsource (lib "eagle-import") (part "R-EU_R0402"))
    )
    (comp (ref "R207")
      (value "4.7k")
      (footprint "eagle-import:R0402")
      (libsource (lib "eagle-import") (part "R-EU_R0402"))
    )
    (comp (ref "R208")
      (value "10k")
      (footprint "eagle-import:R0402")
      (libsource (lib "eagle-import") (part "R-EU_R0402"))
    )
    (comp (ref "R211")
      (value "10k")
      (footprint "eagle-import:R0402")
      (libsource (lib "eagle-import") (part "R-EU_R0402"))
    )
    (comp (ref "SJ1") (value "SJ") (footprint "eagle-import:SJ") (libsource (lib "eagle-import") (part "SJ")))
    (comp (ref "SW1")
      (value "TMPS2-SMD")
      (footprint "eagle-import:FSM2JSMA")
      (libsource (lib "eagle-import") (part "FSM2JSMA"))
    )
    (comp (ref "U$9")
      (value "127MARKED")
      (footprint "eagle-import:PINHEAD_127")
      (libsource (lib "eagle-import") (part "127MARKED"))
    )
    (comp (ref "U$11")
      (value "SEGGER.L_100")
      (footprint "eagle-import:LOGO_100")
      (libsource (lib "eagle-import") (part "SEGGER.L_100"))
    )
    (comp (ref "USB1")
      (value "vertical")
      (footprint "eagle-import:USBVERTICAL")
      (libsource (lib "eagle-import") (part "MICRO_USB_VERTICAL"))
    )
    (comp (ref "V203")
      (value "BAT60A")
      (footprint "eagle-import:SOD323-R")
      (libsource (lib "eagle-import") (part "BAT60"))
    )
    (comp (ref "XMC4200")
      (value "XMC4200_QFN48")
      (footprint "eagle-import:QFN-48-7X7")
      (libsource (lib "eagle-import") (part "XMC4200_QFN48"))
    )
  )
  (nets
    (net (code "1") (name "AGND") (class "Default")
      (node (ref "C16") (pin "2") (pinfunction "2_2") (pintype "passive"))
      (node (ref "C17") (pin "2") (pinfunction "2_2") (pintype "passive"))
      (node (ref "XMC4500") (pin "32") (pinfunction "VAGND_32") (pintype "bidirectional"))
      (node (ref "XMC4500") (pin "34") (pinfunction "VSSA_34") (pintype "bidirectional"))
    )
    (net (code "2") (name "AUX_LED#") (class "Default")
      (node (ref "LED8") (pin "C") (pinfunction "C_C") (pintype "passive"))
      (node (ref "XMC4200") (pin "1") (pinfunction "P0.1_1") (pintype "bidirectional"))
    )
    (net (code "3") (name "COOLING") (class "Default")
      (node (ref "VREG1") (pin "9") (pinfunction "9_9") (pintype "bidirectional"))
    )
    (net (code "4") (name "CS") (class "Default")
      (node (ref "XMC4200") (pin "23") (pinfunction "P2.3_23") (pintype "bidirectional"))
      (node (ref "XMC4200") (pin "40") (pinfunction "P1.0_40") (pintype "bidirectional"))
    )
    (net (code "5") (name "DBGPRES#") (class "Default")
      (node (ref "CON2") (pin "9") (pinfunction "9_9") (pintype "passive"))
      (node (ref "JP2") (pin "1") (pinfunction "1_1") (pintype "passive"))
      (node (ref "R211") (pin "1") (pinfunction "1_1") (pintype "passive"))
      (node (ref "U$9") (pin "P$4") (pinfunction "P$4_P$4") (pintype "bidirectional"))
      (node (ref "XMC4200") (pin "32") (pinfunction "PORST#_32") (pintype "bidirectional"))
    )
    (net (code "6") (name "DEBUG_LED#") (class "Default")
      (node (ref "LED7") (pin "C") (pinfunction "C_C") (pintype "passive"))
      (node (ref "XMC4200") (pin "48") (pinfunction "P0.2_48") (pintype "bidirectional"))
    )
    (net (code "7") (name "DEBUG_RX_XMC42{slash}TX_XMC45") (class "Default")
      (node (ref "SJ6") (pin "2") (pinfunction "2_2") (pintype "passive"))
      (node (ref "XMC4200") (pin "46") (pinfunction "P0.4_46") (pintype "bidirectional"))
    )
    (net (code "8") (name "DEBUG_TX_XMC42{slash}RX_XMC45") (class "Default")
      (node (ref "R25") (pin "2") (pinfunction "2_2") (pintype "passive"))
      (node (ref "SJ5") (pin "2") (pinfunction "2_2") (pintype "passive"))
    )
    (net (code "9") (name "GND") (class "Default")
      (node (ref "C1") (pin "2") (pinfunction "2_2") (pintype "passive"))
      (node (ref "C10") (pin "2") (pinfunction "2_2") (pintype "passive"))
      (node (ref "C11") (pin "2") (pinfunction "2_2") (pintype "passive"))
      (node (ref "C12") (pin "2") (pinfunction "2_2") (pintype "passive"))
      (node (ref "C13") (pin "2") (pinfunction "2_2") (pintype "passive"))
      (node (ref "C14") (pin "2") (pinfunction "2_2") (pintype "passive"))
      (node (ref "C15") (pin "1") (pinfunction "1_1") (pintype "passive"))
      (node (ref "C18") (pin "1") (pinfunction "1_1") (pintype "passive"))
      (node (ref "C19") (pin "1") (pinfunction "1_1") (pintype "passive"))
      (node (ref "C2") (pin "2") (pinfunction "2_2") (pintype "passive"))
      (node (ref "C20") (pin "2") (pinfunction "2_2") (pintype "passive"))
      (node (ref "C204") (pin "2") (pinfunction "2_2") (pintype "passive"))
      (node (ref "C205") (pin "2") (pinfunction "2_2") (pintype "passive"))
      (node (ref "C206") (pin "2") (pinfunction "2_2") (pintype "passive"))
      (node (ref "C208") (pin "2") (pinfunction "2_2") (pintype "passive"))
      (node (ref "C209") (pin "2") (pinfunction "2_2") (pintype "passive"))
      (node (ref "C21") (pin "1") (pinfunction "1_1") (pintype "passive"))
      (node (ref "C210") (pin "2") (pinfunction "2_2") (pintype "passive"))
      (node (ref "C211") (pin "2") (pinfunction "2_2") (pintype "passive"))
      (node (ref "C212") (pin "2") (pinfunction "2_2") (pintype "passive"))
      (node (ref "C213") (pin "2") (pinfunction "2_2") (pintype "passive"))
      (node (ref "C22") (pin "2") (pinfunction "2_2") (pintype "passive"))
      (node (ref "C23") (pin "2") (pinfunction "2_2") (pintype "passive"))
      (node (ref "C24") (pin "1") (pinfunction "1_1") (pintype "passive"))
      (node (ref "C25") (pin "2") (pinfunction "2_2") (pintype "passive"))
      (node (ref "C26") (pin "2") (pinfunction "2_2") (pintype "passive"))
      (node (ref "C27") (pin "2") (pinfunction "2_2") (pintype "passive"))
      (node (ref "C28") (pin "1") (pinfunction "1_1") (pintype "passive"))
      (node (ref "C29") (pin "2") (pinfunction "2_2") (pintype "passive"))
      (node (ref "C3") (pin "2") (pinfunction "2_2") (pintype "passive"))
      (node (ref "C30") (pin "2") (pinfunction "2_2") (pintype "passive"))
      (node (ref "C31") (pin "2") (pinfunction "2_2") (pintype "passive"))
      (node (ref "C32") (pin "2") (pinfunction "2_2") (pintype "passive"))
      (node (ref "C33") (pin "1") (pinfunction "1_1") (pintype "passive"))
      (node (ref "C35") (pin "2") (pinfunction "2_2") (pintype "passive"))
      (node (ref "C37") (pin "2") (pinfunction "2_2") (pintype "passive"))
      (node (ref "C38") (pin "2") (pinfunction "2_2") (pintype "passive"))
      (node (ref "C39") (pin "2") (pinfunction "2_2") (pintype "passive"))
      (node (ref "C4") (pin "2") (pinfunction "2_2") (pintype "passive"))
      (node (ref "C40") (pin "2") (pinfunction "2_2") (pintype "passive"))
      (node (ref "C41") (pin "2") (pinfunction "2_2") (pintype "passive"))
      (node (ref "C42") (pin "2") (pinfunction "2_2") (pintype "passive"))
      (node (ref "C43") (pin "2") (pinfunction "2_2") (pintype "passive"))
      (node (ref "C5") (pin "2") (pinfunction "2_2") (pintype "passive"))
      (node (ref "C6") (pin "2") (pinfunction "2_2") (pintype "passive"))
      (node (ref "C7") (pin "2") (pinfunction "2_2") (pintype "passive"))
      (node (ref "C8") (pin "2") (pinfunction "2_2") (pintype "passive"))
      (node (ref "C9") (pin "2") (pinfunction "2_2") (pintype "passive"))
      (node (ref "CON10") (pin "1") (pinfunction "1_1") (pintype "passive"))
      (node (ref "CON12") (pin "2") (pinfunction "2_2") (pintype "passive"))
      (node (ref "CON14") (pin "2") (pinfunction "2_2") (pintype "passive"))
      (node (ref "CON15") (pin "2") (pinfunction "2_2") (pintype "passive"))
      (node (ref "CON2") (pin "3") (pinfunction "3_3") (pintype "passive"))
      (node (ref "CON2") (pin "5") (pinfunction "5_5") (pintype "passive"))
      (node (ref "CON3") (pin "1") (pinfunction "1_1") (pintype "passive"))
      (node (ref "CON4") (pin "2") (pinfunction "2_2") (pintype "passive"))
      (node (ref "CON9") (pin "1") (pinfunction "1_1") (pintype "passive"))
      (node (ref "CON9") (pin "3") (pinfunction "3_3") (pintype "passive"))
      (node (ref "D1") (pin "3") (pinfunction "3_3") (pintype "passive"))
      (node (ref "D3") (pin "P$1") (pinfunction "P$1_P$1") (pintype "bidirectional"))
      (node (ref "D4") (pin "P$1") (pinfunction "P$1_P$1") (pintype "bidirectional"))
      (node (ref "D6") (pin "1") (pinfunction "1_1") (pintype "bidirectional"))
      (node (ref "D7") (pin "3") (pinfunction "3_3") (pintype "passive"))
      (node (ref "DPS310") (pin "P1") (pinfunction "GND1_P1") (pintype "bidirectional"))
      (node (ref "DPS310") (pin "P7") (pinfunction "GND2_P7") (pintype "bidirectional"))
      (node (ref "IC1") (pin "4") (pinfunction "GND_4") (pintype "bidirectional"))
      (node (ref "IC2") (pin "4") (pinfunction "GND_4") (pintype "bidirectional"))
      (node (ref "JP2") (pin "2") (pinfunction "2_2") (pintype "passive"))
      (node (ref "LD1") (pin "P_4") (pinfunction "P4/GND_P_4") (pintype "bidirectional"))
      (node (ref "LD2") (pin "P_4") (pinfunction "P4/GND_P_4") (pintype "bidirectional"))
      (node (ref "LD3") (pin "P_4") (pinfunction "P4/GND_P_4") (pintype "bidirectional"))
      (node (ref "LD4") (pin "P_4") (pinfunction "P4/GND_P_4") (pintype "bidirectional"))
      (node (ref "LED1") (pin "C") (pinfunction "C_C") (pintype "passive"))
      (node (ref "LED2") (pin "C") (pinfunction "C_C") (pintype "passive"))
      (node (ref "LED3") (pin "C") (pinfunction "C_C") (pintype "passive"))
      (node (ref "LED4") (pin "C") (pinfunction "C_C") (pintype "passive"))
      (node (ref "LED5") (pin "C") (pinfunction "C_C") (pintype "passive"))
      (node (ref "LED6") (pin "C") (pinfunction "C_C") (pintype "passive"))
      (node (ref "M1_IN") (pin "1") (pinfunction "1_1") (pintype "passive"))
      (node (ref "M1_IN") (pin "2") (pinfunction "2_2") (pintype "passive"))
      (node (ref "M1_OUT") (pin "7") (pinfunction "7_7") (pintype "passive"))
      (node (ref "M1_OUT") (pin "8") (pinfunction "8_8") (pintype "passive"))
      (node (ref "M2_IN") (pin "1") (pinfunction "1_1") (pintype "passive"))
      (node (ref "M2_IN") (pin "2") (pinfunction "2_2") (pintype "passive"))
      (node (ref "M2_OUT") (pin "7") (pinfunction "7_7") (pintype "passive"))
      (node (ref "M2_OUT") (pin "8") (pinfunction "8_8") (pintype "passive"))
      (node (ref "M3_IN") (pin "1") (pinfunction "1_1") (pintype "passive"))
      (node (ref "M3_IN") (pin "2") (pinfunction "2_2") (pintype "passive"))
      (node (ref "M3_OUT") (pin "7") (pinfunction "7_7") (pintype "passive"))
      (node (ref "M3_OUT") (pin "8") (pinfunction "8_8") (pintype "passive"))
      (node (ref "M4_IN") (pin "1") (pinfunction "1_1") (pintype "passive"))
      (node (ref "M4_IN") (pin "2") (pinfunction "2_2") (pintype "passive"))
      (node (ref "M4_OUT") (pin "7") (pinfunction "7_7") (pintype "passive"))
      (node (ref "M4_OUT") (pin "8") (pinfunction "8_8") (pintype "passive"))
      (node (ref "MPU9250") (pin "11") (pinfunction "11_11") (pintype "bidirectional"))
      (node (ref "MPU9250") (pin "18") (pinfunction "18_18") (pintype "bidirectional"))
      (node (ref "MPU9250") (pin "20") (pinfunction "20_20") (pintype "bidirectional"))
      (node (ref "ORIGA") (pin "A1") (pinfunction "A1/VSS_A1") (pintype "bidirectional"))
      (node (ref "ORIGA") (pin "A2") (pinfunction "A2/VSS_A2") (pintype "bidirectional"))
      (node (ref "ORIGA") (pin "C1") (pinfunction "C1/VSS_C1") (pintype "bidirectional"))
      (node (ref "PAD2") (pin "P$1") (pinfunction "P$1_P$1") (pintype "bidirectional"))
      (node (ref "R18") (pin "2") (pinfunction "2_2") (pintype "passive"))
      (node (ref "R19") (pin "2") (pinfunction "2_2") (pintype "passive"))
      (node (ref "R208") (pin "1") (pinfunction "1_1") (pintype "passive"))
      (node (ref "R24") (pin "2") (pinfunction "2_2") (pintype "passive"))
      (node (ref "R26") (pin "2") (pinfunction "2_2") (pintype "passive"))
      (node (ref "R27") (pin "2") (pinfunction "2_2") (pintype "passive"))
      (node (ref "R30") (pin "2") (pinfunction "2_2") (pintype "passive"))
      (node (ref "R32") (pin "2") (pinfunction "2_2") (pintype "passive"))
      (node (ref "R33") (pin "2") (pinfunction "2_2") (pintype "passive"))
      (node (ref "R7") (pin "2") (pinfunction "2_2") (pintype "passive"))
      (node (ref "RN42") (pin "GND1") (pinfunction "1_GND_GND1") (pintype "bidirectional"))
      (node (ref "RN42") (pin "GND2") (pinfunction "12_GND_GND2") (pintype "bidirectional"))
      (node (ref "RN42") (pin "GND3") (pinfunction "29_GND_GND3") (pintype "bidirectional"))
      (node (ref "RN42") (pin "GND4") (pinfunction "28_GND_GND4") (pintype "bidirectional"))
      (node (ref "SW1") (pin "S") (pinfunction "S_S") (pintype "passive"))
      (node (ref "SW1") (pin "S1") (pinfunction "S_S1") (pintype "passive"))
      (node (ref "U$9") (pin "P$5") (pinfunction "P$5_P$5") (pintype "bidirectional"))
      (node (ref "USB") (pin "1") (pinfunction "1_1") (pintype "passive"))
      (node (ref "USB1") (pin "1") (pinfunction "1_1") (pintype "passive"))
      (node (ref "VREG1") (pin "1") (pinfunction "1_1") (pintype "bidirectional"))
      (node (ref "VREG1") (pin "2") (pinfunction "2_2") (pintype "bidirectional"))
      (node (ref "VREG2") (pin "1") (pinfunction "ADJ_1") (pintype "power_in"))
      (node (ref "XMC4200") (pin "11") (pinfunction "P14.7_11") (pintype "bidirectional"))
      (node (ref "XMC4200") (pin "12") (pinfunction "P14.6_12") (pintype "bidirectional"))
      (node (ref "XMC4200") (pin "13") (pinfunction "P14.5_13") (pintype "bidirectional"))
      (node (ref "XMC4200") (pin "14") (pinfunction "P14.4_14") (pintype "bidirectional"))
      (node (ref "XMC4200") (pin "17") (pinfunction "VAGND_17") (pintype "bidirectional"))
      (node (ref "XMC4200") (pin "20") (pinfunction "P14.8_20") (pintype "bidirectional"))
      (node (ref "XMC4200") (pin "27") (pinfunction "VSS_27") (pintype "bidirectional"))
      (node (ref "XMC4200") (pin "EPAD") (pinfunction "EPAD_EPAD") (pintype "bidirectional"))
      (node (ref "XMC4500") (pin "59") (pinfunction "VSS_59") (pintype "bidirectional"))
      (node (ref "XMC4500") (pin "63") (pinfunction "VSSO_63") (pintype "bidirectional"))
      (node (ref "XMC4500") (pin "EXP") (pinfunction "EPAD_EXP") (pintype "bidirectional"))
    )
    (net (code "10") (name "HIB_IO_0") (class "Default")
      (node (ref "XMC4500") (pin "14") (pinfunction "HIB_IO_0_14") (pintype "bidirectional"))
    )
    (net (code "11") (name "HIB_IO_1") (class "Default")
      (node (ref "XMC4500") (pin "13") (pinfunction "HIB_IO_1_13") (pintype "bidirectional"))
    )
    (net (code "12") (name "LEDOUT1") (class "Default")
      (node (ref "EL1") (pin "2") (pinfunction "2_2") (pintype "passive"))
      (node (ref "LD1") (pin "P_2") (pinfunction "P2/OUT_P_2") (pintype "bidirectional"))
      (node (ref "LD1") (pin "P_3") (pinfunction "P3/OUT_P_3") (pintype "bidirectional"))
      (node (ref "LD1") (pin "P_5") (pinfunction "P5/OUT_P_5") (pintype "bidirectional"))
    )
    (net (code "13") (name "LEDOUT2") (class "Default")
      (node (ref "EL2") (pin "2") (pinfunction "2_2") (pintype "passive"))
      (node (ref "LD2") (pin "P_2") (pinfunction "P2/OUT_P_2") (pintype "bidirectional"))
      (node (ref "LD2") (pin "P_3") (pinfunction "P3/OUT_P_3") (pintype "bidirectional"))
      (node (ref "LD2") (pin "P_5") (pinfunction "P5/OUT_P_5") (pintype "bidirectional"))
    )
    (net (code "14") (name "LEDOUT3") (class "Default")
      (node (ref "EL4") (pin "2") (pinfunction "2_2") (pintype "passive"))
      (node (ref "LD4") (pin "P_2") (pinfunction "P2/OUT_P_2") (pintype "bidirectional"))
      (node (ref "LD4") (pin "P_3") (pinfunction "P3/OUT_P_3") (pintype "bidirectional"))
      (node (ref "LD4") (pin "P_5") (pinfunction "P5/OUT_P_5") (pintype "bidirectional"))
    )
    (net (code "15") (name "LEDOUT4") (class "Default")
      (node (ref "EL3") (pin "2") (pinfunction "2_2") (pintype "passive"))
      (node (ref "LD3") (pin "P_2") (pinfunction "P2/OUT_P_2") (pintype "bidirectional"))
      (node (ref "LD3") (pin "P_3") (pinfunction "P3/OUT_P_3") (pintype "bidirectional"))
      (node (ref "LD3") (pin "P_5") (pinfunction "P5/OUT_P_5") (pintype "bidirectional"))
    )
    (net (code "16") (name "Net-(C19-Pad2)") (class "Default")
      (node (ref "C19") (pin "2") (pinfunction "2_2") (pintype "passive"))
      (node (ref "MPU9250") (pin "10") (pinfunction "10_10") (pintype "bidirectional"))
    )
    (net (code "17") (name "Net-(C34-Pad2)") (class "Default")
      (node (ref "C34") (pin "2") (pinfunction "2_2") (pintype "passive"))
      (node (ref "VREG1") (pin "5") (pinfunction "5_5") (pintype "bidirectional"))
    )
    (net (code "18") (name "Net-(C36-Pad1)") (class "Default")
      (node (ref "C36") (pin "1") (pinfunction "1_1") (pintype "passive"))
      (node (ref "VREG1") (pin "3") (pinfunction "3_3") (pintype "bidirectional"))
    )
    (net (code "19") (name "Net-(C36-Pad2)") (class "Default")
      (node (ref "C36") (pin "2") (pinfunction "2_2") (pintype "passive"))
      (node (ref "R24") (pin "1") (pinfunction "1_1") (pintype "passive"))
    )
    (net (code "20") (name "Net-(C205-Pad1)") (class "Default")
      (node (ref "C205") (pin "1") (pinfunction "1_1") (pintype "passive"))
      (node (ref "Q2") (pin "1") (pinfunction "1_1") (pintype "passive"))
      (node (ref "R205") (pin "2") (pinfunction "2_2") (pintype "passive"))
    )
    (net (code "21") (name "Net-(CON5-Pad1)") (class "Default")
      (node (ref "CON5") (pin "1") (pinfunction "1_1") (pintype "passive"))
      (node (ref "M1_OUT") (pin "5") (pinfunction "5_5") (pintype "passive"))
      (node (ref "M1_OUT") (pin "6") (pinfunction "6_6") (pintype "passive"))
    )
    (net (code "22") (name "Net-(CON5-Pad2)") (class "Default")
      (node (ref "CON5") (pin "2") (pinfunction "2_2") (pintype "passive"))
      (node (ref "M1_OUT") (pin "3") (pinfunction "3_3") (pintype "passive"))
      (node (ref "M1_OUT") (pin "4") (pinfunction "4_4") (pintype "passive"))
    )
    (net (code "23") (name "Net-(CON5-Pad3)") (class "Default")
      (node (ref "CON5") (pin "3") (pinfunction "3_3") (pintype "passive"))
      (node (ref "M1_OUT") (pin "1") (pinfunction "1_1") (pintype "passive"))
      (node (ref "M1_OUT") (pin "2") (pinfunction "2_2") (pintype "passive"))
    )
    (net (code "24") (name "Net-(CON6-Pad1)") (class "Default")
      (node (ref "CON6") (pin "1") (pinfunction "1_1") (pintype "passive"))
      (node (ref "M2_OUT") (pin "5") (pinfunction "5_5") (pintype "passive"))
      (node (ref "M2_OUT") (pin "6") (pinfunction "6_6") (pintype "passive"))
    )
    (net (code "25") (name "Net-(CON6-Pad2)") (class "Default")
      (node (ref "CON6") (pin "2") (pinfunction "2_2") (pintype "passive"))
      (node (ref "M2_OUT") (pin "3") (pinfunction "3_3") (pintype "passive"))
      (node (ref "M2_OUT") (pin "4") (pinfunction "4_4") (pintype "passive"))
    )
    (net (code "26") (name "Net-(CON6-Pad3)") (class "Default")
      (node (ref "CON6") (pin "3") (pinfunction "3_3") (pintype "passive"))
      (node (ref "M2_OUT") (pin "1") (pinfunction "1_1") (pintype "passive"))
      (node (ref "M2_OUT") (pin "2") (pinfunction "2_2") (pintype "passive"))
    )
    (net (code "27") (name "Net-(CON7-Pad1)") (class "Default")
      (node (ref "CON7") (pin "1") (pinfunction "1_1") (pintype "passive"))
      (node (ref "M3_OUT") (pin "5") (pinfunction "5_5") (pintype "passive"))
      (node (ref "M3_OUT") (pin "6") (pinfunction "6_6") (pintype "passive"))
    )
    (net (code "28") (name "Net-(CON7-Pad2)") (class "Default")
      (node (ref "CON7") (pin "2") (pinfunction "2_2") (pintype "passive"))
      (node (ref "M3_OUT") (pin "3") (pinfunction "3_3") (pintype "passive"))
      (node (ref "M3_OUT") (pin "4") (pinfunction "4_4") (pintype "passive"))
    )
    (net (code "29") (name "Net-(CON7-Pad3)") (class "Default")
      (node (ref "CON7") (pin "3") (pinfunction "3_3") (pintype "passive"))
      (node (ref "M3_OUT") (pin "1") (pinfunction "1_1") (pintype "passive"))
      (node (ref "M3_OUT") (pin "2") (pinfunction "2_2") (pintype "passive"))
    )
    (net (code "30") (name "Net-(CON8-Pad1)") (class "Default")
      (node (ref "CON8") (pin "1") (pinfunction "1_1") (pintype "passive"))
      (node (ref "M4_OUT") (pin "5") (pinfunction "5_5") (pintype "passive"))
      (node (ref "M4_OUT") (pin "6") (pinfunction "6_6") (pintype "passive"))
    )
    (net (code "31") (name "Net-(CON8-Pad2)") (class "Default")
      (node (ref "CON8") (pin "2") (pinfunction "2_2") (pintype "passive"))
      (node (ref "M4_OUT") (pin "3") (pinfunction "3_3") (pintype "passive"))
      (node (ref "M4_OUT") (pin "4") (pinfunction "4_4") (pintype "passive"))
    )
    (net (code "32") (name "Net-(CON8-Pad3)") (class "Default")
      (node (ref "CON8") (pin "3") (pinfunction "3_3") (pintype "passive"))
      (node (ref "M4_OUT") (pin "1") (pinfunction "1_1") (pintype "passive"))
      (node (ref "M4_OUT") (pin "2") (pinfunction "2_2") (pintype "passive"))
    )
    (net (code "33") (name "Net-(CON11-Pad1)") (class "Default")
      (node (ref "CON11") (pin "1") (pinfunction "1_1") (pintype "passive"))
      (node (ref "R13") (pin "1") (pinfunction "1_1") (pintype "passive"))
    )
    (net (code "34") (name "Net-(CON11-Pad2)") (class "Default")
      (node (ref "CON11") (pin "2") (pinfunction "2_2") (pintype "passive"))
      (node (ref "R28") (pin "1") (pinfunction "1_1") (pintype "passive"))
    )
    (net (code "35") (name "Net-(CON11-Pad3)") (class "Default")
      (node (ref "CON11") (pin "3") (pinfunction "3_3") (pintype "passive"))
      (node (ref "R29") (pin "1") (pinfunction "1_1") (pintype "passive"))
    )
    (net (code "36") (name "Net-(D1-Pad2)") (class "Default")
      (node (ref "D1") (pin "2") (pinfunction "2_2") (pintype "passive"))
      (node (ref "R10") (pin "1") (pinfunction "1_1") (pintype "passive"))
      (node (ref "USB") (pin "4") (pinfunction "4_4") (pintype "passive"))
    )
    (net (code "37") (name "Net-(D4-PadP$2)") (class "Default")
      (node (ref "D4") (pin "P$2") (pinfunction "P$2_P$2") (pintype "bidirectional"))
      (node (ref "JP1") (pin "1") (pinfunction "1_1") (pintype "passive"))
      (node (ref "R3") (pin "2") (pinfunction "2_2") (pintype "passive"))
      (node (ref "R4") (pin "2") (pinfunction "2_2") (pintype "passive"))
      (node (ref "R7") (pin "1") (pinfunction "1_1") (pintype "passive"))
    )
    (net (code "38") (name "Net-(D5-C)") (class "Default")
      (node (ref "CON2") (pin "10") (pinfunction "10_10") (pintype "passive"))
      (node (ref "D5") (pin "1") (pinfunction "C_1") (pintype "passive"))
    )
    (net (code "39") (name "Net-(D7-Pad1)") (class "Default")
      (node (ref "D7") (pin "1") (pinfunction "1_1") (pintype "passive"))
      (node (ref "R204") (pin "2") (pinfunction "2_2") (pintype "passive"))
      (node (ref "USB1") (pin "4") (pinfunction "4_4") (pintype "passive"))
    )
    (net (code "40") (name "Net-(L1-Pad2)") (class "Default")
      (node (ref "L1") (pin "2") (pinfunction "2_2") (pintype "passive"))
      (node (ref "USB") (pin "5") (pinfunction "5_5") (pintype "passive"))
    )
    (net (code "41") (name "Net-(L4-1)") (class "Default")
      (node (ref "C24") (pin "2") (pinfunction "2_2") (pintype "passive"))
      (node (ref "L4") (pin "P$1") (pinfunction "1_P$1") (pintype "bidirectional"))
      (node (ref "VREG1") (pin "8") (pinfunction "8_8") (pintype "bidirectional"))
    )
    (net (code "42") (name "Net-(L5-1)") (class "Default")
      (node (ref "C34") (pin "1") (pinfunction "1_1") (pintype "passive"))
      (node (ref "D6") (pin "2") (pinfunction "2_2") (pintype "bidirectional"))
      (node (ref "L5") (pin "P$1") (pinfunction "1_P$1") (pintype "bidirectional"))
      (node (ref "VREG1") (pin "6") (pinfunction "6_6") (pintype "bidirectional"))
    )
    (net (code "43") (name "Net-(L6-Pad1)") (class "Default")
      (node (ref "L6") (pin "1") (pinfunction "1_1") (pintype "passive"))
      (node (ref "USB1") (pin "5") (pinfunction "5_5") (pintype "passive"))
    )
    (net (code "44") (name "Net-(L6-Pad2)") (class "Default")
      (node (ref "L6") (pin "2") (pinfunction "2_2") (pintype "passive"))
      (node (ref "R207") (pin "2") (pinfunction "2_2") (pintype "passive"))
      (node (ref "V203") (pin "A") (pinfunction "A_A") (pintype "passive"))
    )
    (net (code "45") (name "Net-(LD1-P6{slash}REXT)") (class "Default")
      (node (ref "LD1") (pin "P_6") (pinfunction "P6/REXT_P_6") (pintype "bidirectional"))
      (node (ref "R27") (pin "1") (pinfunction "1_1") (pintype "passive"))
    )
    (net (code "46") (name "Net-(LD2-P6{slash}REXT)") (class "Default")
      (node (ref "LD2") (pin "P_6") (pinfunction "P6/REXT_P_6") (pintype "bidirectional"))
      (node (ref "R26") (pin "1") (pinfunction "1_1") (pintype "passive"))
    )
    (net (code "47") (name "Net-(LD3-P6{slash}REXT)") (class "Default")
      (node (ref "LD3") (pin "P_6") (pinfunction "P6/REXT_P_6") (pintype "bidirectional"))
      (node (ref "R32") (pin "1") (pinfunction "1_1") (pintype "passive"))
    )
    (net (code "48") (name "Net-(LD4-P6{slash}REXT)") (class "Default")
      (node (ref "LD4") (pin "P_6") (pinfunction "P6/REXT_P_6") (pintype "bidirectional"))
      (node (ref "R33") (pin "1") (pinfunction "1_1") (pintype "passive"))
    )
    (net (code "49") (name "Net-(LED1-PadA)") (class "Default")
      (node (ref "LED1") (pin "A") (pinfunction "A_A") (pintype "passive"))
      (node (ref "R6") (pin "1") (pinfunction "1_1") (pintype "passive"))
    )
    (net (code "50") (name "Net-(LED2-PadA)") (class "Default")
      (node (ref "LED2") (pin "A") (pinfunction "A_A") (pintype "passive"))
      (node (ref "R20") (pin "1") (pinfunction "1_1") (pintype "passive"))
    )
    (net (code "51") (name "Net-(LED3-PadA)") (class "Default")
      (node (ref "LED3") (pin "A") (pinfunction "A_A") (pintype "passive"))
      (node (ref "R21") (pin "1") (pinfunction "1_1") (pintype "passive"))
    )
    (net (code "52") (name "Net-(LED4-PadA)") (class "Default")
      (node (ref "LED4") (pin "A") (pinfunction "A_A") (pintype "passive"))
      (node (ref "R22") (pin "1") (pinfunction "1_1") (pintype "passive"))
    )
    (net (code "53") (name "Net-(LED5-PadA)") (class "Default")
      (node (ref "LED5") (pin "A") (pinfunction "A_A") (pintype "passive"))
      (node (ref "R23") (pin "1") (pinfunction "1_1") (pintype "passive"))
    )
    (net (code "54") (name "Net-(LED6-PadA)") (class "Default")
      (node (ref "LED6") (pin "A") (pinfunction "A_A") (pintype "passive"))
      (node (ref "R5") (pin "1") (pinfunction "1_1") (pintype "passive"))
    )
    (net (code "55") (name "Net-(LED7-PadA)") (class "Default")
      (node (ref "LED7") (pin "A") (pinfunction "A_A") (pintype "passive"))
      (node (ref "R201") (pin "2") (pinfunction "2_2") (pintype "passive"))
    )
    (net (code "56") (name "Net-(LED8-PadA)") (class "Default")
      (node (ref "LED8") (pin "A") (pinfunction "A_A") (pintype "passive"))
      (node (ref "R202") (pin "2") (pinfunction "2_2") (pintype "passive"))
    )
    (net (code "57") (name "Net-(M1_IN-Pad6)") (class "Default")
      (node (ref "M1_IN") (pin "6") (pinfunction "6_6") (pintype "passive"))
      (node (ref "M2_IN") (pin "5") (pinfunction "5_5") (pintype "passive"))
      (node (ref "R35") (pin "1") (pinfunction "1_1") (pintype "passive"))
    )
    (net (code "58") (name "Net-(M2_IN-Pad6)") (class "Default")
      (node (ref "M2_IN") (pin "6") (pinfunction "6_6") (pintype "passive"))
      (node (ref "M3_IN") (pin "5") (pinfunction "5_5") (pintype "passive"))
      (node (ref "R37") (pin "1") (pinfunction "1_1") (pintype "passive"))
    )
    (net (code "59") (name "Net-(M3_IN-Pad6)") (class "Default")
      (node (ref "M3_IN") (pin "6") (pinfunction "6_6") (pintype "passive"))
      (node (ref "M4_IN") (pin "5") (pinfunction "5_5") (pintype "passive"))
      (node (ref "R38") (pin "1") (pinfunction "1_1") (pintype "passive"))
    )
    (net (code "60") (name "Net-(ORIGA-B2{slash}VDD)") (class "Default")
      (node (ref "C28") (pin "2") (pinfunction "2_2") (pintype "passive"))
      (node (ref "ORIGA") (pin "B2") (pinfunction "B2/VDD_B2") (pintype "bidirectional"))
      (node (ref "R2") (pin "2") (pinfunction "2_2") (pintype "passive"))
    )
    (net (code "61") (name "Net-(ORIGA-C2{slash}BIF)") (class "Default")
      (node (ref "ORIGA") (pin "C2") (pinfunction "C2/BIF_C2") (pintype "bidirectional"))
      (node (ref "R3") (pin "1") (pinfunction "1_1") (pintype "passive"))
    )
    (net (code "62") (name "Net-(Q1-2)") (class "Default")
      (node (ref "C13") (pin "1") (pinfunction "1_1") (pintype "passive"))
      (node (ref "Q1") (pin "3") (pinfunction "2_3") (pintype "passive"))
      (node (ref "R12") (pin "2") (pinfunction "2_2") (pintype "passive"))
    )
    (net (code "63") (name "Net-(Q2-2)") (class "Default")
      (node (ref "C206") (pin "1") (pinfunction "1_1") (pintype "passive"))
      (node (ref "Q2") (pin "3") (pinfunction "2_3") (pintype "passive"))
      (node (ref "XMC4200") (pin "29") (pinfunction "XTAL1_29") (pintype "bidirectional"))
    )
    (net (code "64") (name "Net-(RN42-13_RX)") (class "Default")
      (node (ref "RN42") (pin "UART_RX") (pinfunction "13_RX_UART_RX") (pintype "bidirectional"))
      (node (ref "SJ3") (pin "2") (pinfunction "2_2") (pintype "passive"))
    )
    (net (code "65") (name "Net-(RN42-14_TX)") (class "Default")
      (node (ref "RN42") (pin "UART_TX") (pinfunction "14_TX_UART_TX") (pintype "bidirectional"))
      (node (ref "SJ2") (pin "2") (pinfunction "2_2") (pintype "passive"))
    )
    (net (code "66") (name "Net-(RN42-15_RTS)") (class "Default")
      (node (ref "RN42") (pin "UART_CTX") (pinfunction "16_CTS_UART_CTX") (pintype "bidirectional"))
      (node (ref "RN42") (pin "UART_RTX") (pinfunction "15_RTS_UART_RTX") (pintype "bidirectional"))
    )
    (net (code "67") (name "Net-(RN42-19_LED)") (class "Default")
      (node (ref "R6") (pin "2") (pinfunction "2_2") (pintype "passive"))
      (node (ref "RN42") (pin "GPIO_2") (pinfunction "19_LED_GPIO_2") (pintype "bidirectional"))
    )
    (net (code "68") (name "Net-(USB-3)") (class "Default")
      (node (ref "D1") (pin "1") (pinfunction "1_1") (pintype "passive"))
      (node (ref "R11") (pin "1") (pinfunction "1_1") (pintype "passive"))
      (node (ref "USB") (pin "3+") (pinfunction "3_3+") (pintype "passive"))
    )
    (net (code "69") (name "Net-(USB1-3)") (class "Default")
      (node (ref "D7") (pin "2") (pinfunction "2_2") (pintype "passive"))
      (node (ref "R206") (pin "2") (pinfunction "2_2") (pintype "passive"))
      (node (ref "USB1") (pin "3+") (pinfunction "3_3+") (pintype "passive"))
    )
    (net (code "70") (name "Net-(XMC4200-HIB_IO_0)") (class "Default")
      (node (ref "R207") (pin "1") (pinfunction "1_1") (pintype "passive"))
      (node (ref "R208") (pin "2") (pinfunction "2_2") (pintype "passive"))
      (node (ref "XMC4200") (pin "7") (pinfunction "HIB_IO_0_7") (pintype "bidirectional"))
    )
    (net (code "71") (name "Net-(XMC4200-P0.5)") (class "Default")
      (node (ref "R25") (pin "1") (pinfunction "1_1") (pintype "passive"))
      (node (ref "XMC4200") (pin "45") (pinfunction "P0.5_45") (pintype "bidirectional"))
    )
    (net (code "72") (name "Net-(XMC4200-USB_D+)") (class "Default")
      (node (ref "R206") (pin "1") (pinfunction "1_1") (pintype "passive"))
      (node (ref "XMC4200") (pin "4") (pinfunction "USB_D+_4") (pintype "bidirectional"))
    )
    (net (code "73") (name "Net-(XMC4200-USB_D-)") (class "Default")
      (node (ref "R204") (pin "1") (pinfunction "1_1") (pintype "passive"))
      (node (ref "XMC4200") (pin "3") (pinfunction "USB_D-_3") (pintype "bidirectional"))
    )
    (net (code "74") (name "Net-(XMC4200-VDDC)") (class "Default")
      (node (ref "C208") (pin "1") (pinfunction "1_1") (pintype "passive"))
      (node (ref "C209") (pin "1") (pinfunction "1_1") (pintype "passive"))
      (node (ref "C210") (pin "1") (pinfunction "1_1") (pintype "passive"))
      (node (ref "XMC4200") (pin "31") (pinfunction "VDDC1_31") (pintype "bidirectional"))
      (node (ref "XMC4200") (pin "6") (pinfunction "VDDC_6") (pintype "bidirectional"))
    )
    (net (code "75") (name "Net-(XMC4200-XTAL2)") (class "Default")
      (node (ref "R205") (pin "1") (pinfunction "1_1") (pintype "passive"))
      (node (ref "XMC4200") (pin "30") (pinfunction "XTAL2_30") (pintype "bidirectional"))
    )
    (net (code "76") (name "Net-(XMC4500-XTAL1)") (class "Default")
      (node (ref "C12") (pin "1") (pinfunction "1_1") (pintype "passive"))
      (node (ref "Q1") (pin "1") (pinfunction "1_1") (pintype "passive"))
      (node (ref "XMC4500") (pin "61") (pinfunction "XTAL1_61") (pintype "bidirectional"))
    )
    (net (code "77") (name "Net-(XMC4500-XTAL2)") (class "Default")
      (node (ref "R12") (pin "1") (pinfunction "1_1") (pintype "passive"))
      (node (ref "XMC4500") (pin "62") (pinfunction "XTAL2_62") (pintype "bidirectional"))
    )
    (net (code "78") (name "P0.0") (class "Default")
      (node (ref "M4_IN") (pin "6") (pinfunction "6_6") (pintype "passive"))
      (node (ref "XMC4500") (pin "2") (pinfunction "P0.0_2") (pintype "bidirectional"))
    )
    (net (code "79") (name "P0.1") (class "Default")
      (node (ref "M1_IN") (pin "5") (pinfunction "5_5") (pintype "passive"))
      (node (ref "R36") (pin "1") (pinfunction "1_1") (pintype "passive"))
      (node (ref "XMC4500") (pin "1") (pinfunction "P0.1_1") (pintype "bidirectional"))
    )
    (net (code "80") (name "P0.2") (class "Default")
      (node (ref "LD1") (pin "P_1") (pinfunction "P1/EN_P_1") (pintype "bidirectional"))
      (node (ref "XMC4500") (pin "100") (pinfunction "P0.2_100") (pintype "bidirectional"))
    )
    (net (code "81") (name "P0.3") (class "Default")
      (node (ref "LD2") (pin "P_1") (pinfunction "P1/EN_P_1") (pintype "bidirectional"))
      (node (ref "XMC4500") (pin "99") (pinfunction "P0.3_99") (pintype "bidirectional"))
    )
    (net (code "82") (name "P0.4") (class "Default")
      (node (ref "CON4") (pin "3") (pinfunction "3_3") (pintype "passive"))
      (node (ref "XMC4500") (pin "98") (pinfunction "P0.4_98") (pintype "bidirectional"))
    )
    (net (code "83") (name "P0.5") (class "Default")
      (node (ref "CON15") (pin "8") (pinfunction "8_8") (pintype "passive"))
      (node (ref "MPU9250") (pin "12") (pinfunction "12_12") (pintype "bidirectional"))
      (node (ref "XMC4500") (pin "97") (pinfunction "P0.5_97") (pintype "bidirectional"))
    )
    (net (code "84") (name "P0.6") (class "Default")
      (node (ref "XMC4500") (pin "96") (pinfunction "P0.6_96") (pintype "bidirectional"))
    )
    (net (code "85") (name "P0.7") (class "Default")
      (node (ref "CON2") (pin "8") (pinfunction "8_8") (pintype "passive"))
      (node (ref "XMC4500") (pin "89") (pinfunction "P0.7_89") (pintype "bidirectional"))
    )
    (net (code "86") (name "P0.8") (class "Default")
      (node (ref "XMC4500") (pin "88") (pinfunction "P0.8_88") (pintype "bidirectional"))
    )
    (net (code "87") (name "P0.9") (class "Default")
      (node (ref "R20") (pin "2") (pinfunction "2_2") (pintype "passive"))
      (node (ref "XMC4500") (pin "4") (pinfunction "P0.9_4") (pintype "bidirectional"))
    )
    (net (code "88") (name "P0.10") (class "Default")
      (node (ref "JP1") (pin "2") (pinfunction "2_2") (pintype "passive"))
      (node (ref "XMC4500") (pin "3") (pinfunction "P0.10_3") (pintype "bidirectional"))
    )
    (net (code "89") (name "P0.11") (class "Default")
      (node (ref "XMC4500") (pin "95") (pinfunction "P0.11_95") (pintype "bidirectional"))
    )
    (net (code "90") (name "P0.12") (class "Default")
      (node (ref "XMC4500") (pin "94") (pinfunction "P0.12_94") (pintype "bidirectional"))
    )
    (net (code "91") (name "P1.0") (class "Default")
      (node (ref "IC1") (pin "2") (pinfunction "A1_2") (pintype "bidirectional"))
      (node (ref "XMC4500") (pin "79") (pinfunction "P1.0_79") (pintype "bidirectional"))
    )
    (net (code "92") (name "P1.1") (class "Default")
      (node (ref "IC1") (pin "3") (pinfunction "A2_3") (pintype "bidirectional"))
      (node (ref "XMC4500") (pin "78") (pinfunction "P1.1_78") (pintype "bidirectional"))
    )
    (net (code "93") (name "P1.2") (class "Default")
      (node (ref "IC2") (pin "2") (pinfunction "A1_2") (pintype "bidirectional"))
      (node (ref "XMC4500") (pin "77") (pinfunction "P1.2_77") (pintype "bidirectional"))
    )
    (net (code "94") (name "P1.3") (class "Default")
      (node (ref "IC2") (pin "3") (pinfunction "A2_3") (pintype "bidirectional"))
      (node (ref "XMC4500") (pin "76") (pinfunction "P1.3_76") (pintype "bidirectional"))
    )
    (net (code "95") (name "P1.4") (class "Default")
      (node (ref "SJ5") (pin "1") (pinfunction "1_1") (pintype "passive"))
      (node (ref "XMC4500") (pin "75") (pinfunction "P1.4_75") (pintype "bidirectional"))
    )
    (net (code "96") (name "P1.5") (class "Default")
      (node (ref "CON10") (pin "2") (pinfunction "2_2") (pintype "passive"))
      (node (ref "R8") (pin "2") (pinfunction "2_2") (pintype "passive"))
      (node (ref "SJ2") (pin "1") (pinfunction "1_1") (pintype "passive"))
      (node (ref "SJ6") (pin "1") (pinfunction "1_1") (pintype "passive"))
      (node (ref "XMC4500") (pin "74") (pinfunction "P1.5_74") (pintype "bidirectional"))
    )
    (net (code "97") (name "P1.6") (class "Default")
      (node (ref "XMC4500") (pin "83") (pinfunction "P1.6_83") (pintype "bidirectional"))
    )
    (net (code "98") (name "P1.7") (class "Default")
      (node (ref "XMC4500") (pin "82") (pinfunction "P1.7_82") (pintype "bidirectional"))
    )
    (net (code "99") (name "P1.8") (class "Default")
      (node (ref "XMC4500") (pin "81") (pinfunction "P1.8_81") (pintype "bidirectional"))
    )
    (net (code "100") (name "P1.9") (class "Default")
      (node (ref "XMC4500") (pin "80") (pinfunction "P1.9_80") (pintype "bidirectional"))
    )
    (net (code "101") (name "P1.10") (class "Default")
      (node (ref "XMC4500") (pin "73") (pinfunction "P1.10_73") (pintype "bidirectional"))
    )
    (net (code "102") (name "P1.11") (class "Default")
      (node (ref "XMC4500") (pin "72") (pinfunction "P1.11_72") (pintype "bidirectional"))
    )
    (net (code "103") (name "P1.12") (class "Default")
      (node (ref "XMC4500") (pin "71") (pinfunction "P1.12_71") (pintype "bidirectional"))
    )
    (net (code "104") (name "P1.13") (class "Default")
      (node (ref "XMC4500") (pin "70") (pinfunction "P1.13_70") (pintype "bidirectional"))
    )
    (net (code "105") (name "P1.14") (class "Default")
      (node (ref "XMC4500") (pin "69") (pinfunction "P1.14_69") (pintype "bidirectional"))
    )
    (net (code "106") (name "P1.15") (class "Default")
      (node (ref "CON13") (pin "3") (pinfunction "3_3") (pintype "passive"))
      (node (ref "DPS310") (pin "P5") (pinfunction "SDO_P5") (pintype "bidirectional"))
      (node (ref "XMC4500") (pin "68") (pinfunction "P1.15_68") (pintype "bidirectional"))
    )
    (net (code "107") (name "P2.0") (class "Default")
      (node (ref "XMC4500") (pin "52") (pinfunction "P2.0_52") (pintype "bidirectional"))
    )
    (net (code "108") (name "P2.2") (class "Default")
      (node (ref "LD4") (pin "P_1") (pinfunction "P1/EN_P_1") (pintype "bidirectional"))
      (node (ref "XMC4500") (pin "50") (pinfunction "P2.2_50") (pintype "bidirectional"))
    )
    (net (code "109") (name "P2.3") (class "Default")
      (node (ref "LD3") (pin "P_1") (pinfunction "P1/EN_P_1") (pintype "bidirectional"))
      (node (ref "XMC4500") (pin "49") (pinfunction "P2.3_49") (pintype "bidirectional"))
    )
    (net (code "110") (name "P2.4") (class "Default")
      (node (ref "CON13") (pin "2") (pinfunction "2_2") (pintype "passive"))
      (node (ref "DPS310") (pin "P4") (pinfunction "SCK_P4") (pintype "bidirectional"))
      (node (ref "R16") (pin "2") (pinfunction "2_2") (pintype "passive"))
      (node (ref "XMC4500") (pin "48") (pinfunction "P2.4_48") (pintype "bidirectional"))
    )
    (net (code "111") (name "P2.5") (class "Default")
      (node (ref "CON13") (pin "1") (pinfunction "1_1") (pintype "passive"))
      (node (ref "DPS310") (pin "P3") (pinfunction "SDI_P3") (pintype "bidirectional"))
      (node (ref "R17") (pin "2") (pinfunction "2_2") (pintype "passive"))
      (node (ref "XMC4500") (pin "47") (pinfunction "P2.5_47") (pintype "bidirectional"))
    )
    (net (code "112") (name "P2.6") (class "Default")
      (node (ref "XMC4500") (pin "54") (pinfunction "P2.6_54") (pintype "bidirectional"))
    )
    (net (code "113") (name "P2.7") (class "Default")
      (node (ref "XMC4500") (pin "53") (pinfunction "P2.7_53") (pintype "bidirectional"))
    )
    (net (code "114") (name "P2.8") (class "Default")
      (node (ref "XMC4500") (pin "46") (pinfunction "P2.8_46") (pintype "bidirectional"))
    )
    (net (code "115") (name "P2.9") (class "Default")
      (node (ref "XMC4500") (pin "45") (pinfunction "P2.9_45") (pintype "bidirectional"))
    )
    (net (code "116") (name "P2.10") (class "Default")
      (node (ref "XMC4500") (pin "44") (pinfunction "P2.10_44") (pintype "bidirectional"))
    )
    (net (code "117") (name "P2.14") (class "Default")
      (node (ref "XMC4500") (pin "41") (pinfunction "P2.14_41") (pintype "bidirectional"))
    )
    (net (code "118") (name "P2.15") (class "Default")
      (node (ref "XMC4500") (pin "40") (pinfunction "P2.15_40") (pintype "bidirectional"))
    )
    (net (code "119") (name "P3.0") (class "Default")
      (node (ref "R22") (pin "2") (pinfunction "2_2") (pintype "passive"))
      (node (ref "XMC4500") (pin "7") (pinfunction "P3.0_7") (pintype "bidirectional"))
    )
    (net (code "120") (name "P3.1") (class "Default")
      (node (ref "R23") (pin "2") (pinfunction "2_2") (pintype "passive"))
      (node (ref "XMC4500") (pin "6") (pinfunction "P3.1_6") (pintype "bidirectional"))
    )
    (net (code "121") (name "P3.2") (class "Default")
      (node (ref "R21") (pin "2") (pinfunction "2_2") (pintype "passive"))
      (node (ref "XMC4500") (pin "5") (pinfunction "P3.2_5") (pintype "bidirectional"))
    )
    (net (code "122") (name "P3.3") (class "Default")
      (node (ref "XMC4500") (pin "93") (pinfunction "P3.3_93") (pintype "bidirectional"))
    )
    (net (code "123") (name "P3.4") (class "Default")
      (node (ref "XMC4500") (pin "92") (pinfunction "P3.4_92") (pintype "bidirectional"))
    )
    (net (code "124") (name "P3.5") (class "Default")
      (node (ref "CON3") (pin "3") (pinfunction "3_3") (pintype "passive"))
      (node (ref "XMC4500") (pin "91") (pinfunction "P3.5_91") (pintype "bidirectional"))
    )
    (net (code "125") (name "P3.6") (class "Default")
      (node (ref "XMC4500") (pin "90") (pinfunction "P3.6_90") (pintype "bidirectional"))
    )
    (net (code "126") (name "P4.0") (class "Default")
      (node (ref "CON3") (pin "4") (pinfunction "4_4") (pintype "passive"))
      (node (ref "XMC4500") (pin "85") (pinfunction "P4.0_85") (pintype "bidirectional"))
    )
    (net (code "127") (name "P4.1") (class "Default")
      (node (ref "XMC4500") (pin "84") (pinfunction "P4.1_84") (pintype "bidirectional"))
    )
    (net (code "128") (name "P5.0") (class "Default")
      (node (ref "CON15") (pin "4") (pinfunction "4_4") (pintype "passive"))
      (node (ref "MPU9250") (pin "24") (pinfunction "24_24") (pintype "bidirectional"))
      (node (ref "R15") (pin "1") (pinfunction "1_1") (pintype "passive"))
      (node (ref "XMC4500") (pin "58") (pinfunction "P5.0_58") (pintype "bidirectional"))
    )
    (net (code "129") (name "P5.1") (class "Default")
      (node (ref "CON10") (pin "4") (pinfunction "4_4") (pintype "passive"))
      (node (ref "R9") (pin "2") (pinfunction "2_2") (pintype "passive"))
      (node (ref "SJ3") (pin "1") (pinfunction "1_1") (pintype "passive"))
      (node (ref "XMC4500") (pin "57") (pinfunction "P5.1_57") (pintype "bidirectional"))
    )
    (net (code "130") (name "P5.2") (class "Default")
      (node (ref "CON15") (pin "3") (pinfunction "3_3") (pintype "passive"))
      (node (ref "MPU9250") (pin "23") (pinfunction "23_23") (pintype "bidirectional"))
      (node (ref "R14") (pin "1") (pinfunction "1_1") (pintype "passive"))
      (node (ref "XMC4500") (pin "56") (pinfunction "P5.2_56") (pintype "bidirectional"))
    )
    (net (code "131") (name "P5.7") (class "Default")
      (node (ref "XMC4500") (pin "55") (pinfunction "P5.7_55") (pintype "bidirectional"))
    )
    (net (code "132") (name "P14.0") (class "Default")
      (node (ref "XMC4500") (pin "31") (pinfunction "P14.0_31") (pintype "bidirectional"))
    )
    (net (code "133") (name "P14.1") (class "Default")
      (node (ref "XMC4500") (pin "30") (pinfunction "P14.1_30") (pintype "bidirectional"))
    )
    (net (code "134") (name "P14.2") (class "Default")
      (node (ref "XMC4500") (pin "29") (pinfunction "P14.2_29") (pintype "bidirectional"))
    )
    (net (code "135") (name "P14.3") (class "Default")
      (node (ref "XMC4500") (pin "28") (pinfunction "P14.3_28") (pintype "bidirectional"))
    )
    (net (code "136") (name "P14.4") (class "Default")
      (node (ref "XMC4500") (pin "27") (pinfunction "P14.4_27") (pintype "bidirectional"))
    )
    (net (code "137") (name "P14.5") (class "Default")
      (node (ref "C29") (pin "1") (pinfunction "1_1") (pintype "passive"))
      (node (ref "R13") (pin "2") (pinfunction "2_2") (pintype "passive"))
      (node (ref "R18") (pin "1") (pinfunction "1_1") (pintype "passive"))
      (node (ref "XMC4500") (pin "26") (pinfunction "P14.5_26") (pintype "bidirectional"))
    )
    (net (code "138") (name "P14.6") (class "Default")
      (node (ref "XMC4500") (pin "25") (pinfunction "P14.6_25") (pintype "bidirectional"))
    )
    (net (code "139") (name "P14.7") (class "Default")
      (node (ref "C31") (pin "1") (pinfunction "1_1") (pintype "passive"))
      (node (ref "R29") (pin "2") (pinfunction "2_2") (pintype "passive"))
      (node (ref "R30") (pin "1") (pinfunction "1_1") (pintype "passive"))
      (node (ref "XMC4500") (pin "24") (pinfunction "P14.7_24") (pintype "bidirectional"))
    )
    (net (code "140") (name "P14.8") (class "Default")
      (node (ref "C30") (pin "1") (pinfunction "1_1") (pintype "passive"))
      (node (ref "R19") (pin "1") (pinfunction "1_1") (pintype "passive"))
      (node (ref "R28") (pin "2") (pinfunction "2_2") (pintype "passive"))
      (node (ref "XMC4500") (pin "37") (pinfunction "P14.8_37") (pintype "bidirectional"))
    )
    (net (code "141") (name "P14.9") (class "Default")
      (node (ref "XMC4500") (pin "36") (pinfunction "P14.9_36") (pintype "bidirectional"))
    )
    (net (code "142") (name "P14.12") (class "Default")
      (node (ref "XMC4500") (pin "23") (pinfunction "P14.12_23") (pintype "bidirectional"))
    )
    (net (code "143") (name "P14.13") (class "Default")
      (node (ref "XMC4500") (pin "22") (pinfunction "P14.13_22") (pintype "bidirectional"))
    )
    (net (code "144") (name "P14.14") (class "Default")
      (node (ref "XMC4500") (pin "21") (pinfunction "P14.14_21") (pintype "bidirectional"))
    )
    (net (code "145") (name "P14.15") (class "Default")
      (node (ref "XMC4500") (pin "20") (pinfunction "P14.15_20") (pintype "bidirectional"))
    )
    (net (code "146") (name "P15.2") (class "Default")
      (node (ref "XMC4500") (pin "19") (pinfunction "P15.2_19") (pintype "bidirectional"))
    )
    (net (code "147") (name "P15.3") (class "Default")
      (node (ref "XMC4500") (pin "18") (pinfunction "P15.3_18") (pintype "bidirectional"))
    )
    (net (code "148") (name "P15.8") (class "Default")
      (node (ref "XMC4500") (pin "39") (pinfunction "P15.8_39") (pintype "bidirectional"))
    )
    (net (code "149") (name "P15.9") (class "Default")
      (node (ref "XMC4500") (pin "38") (pinfunction "P15.9_38") (pintype "bidirectional"))
    )
    (net (code "150") (name "PWM_MC1") (class "Default")
      (node (ref "IC1") (pin "7") (pinfunction "B1_7") (pintype "bidirectional"))
      (node (ref "R36") (pin "2") (pinfunction "2_2") (pintype "passive"))
    )
    (net (code "151") (name "PWM_MC2") (class "Default")
      (node (ref "IC1") (pin "6") (pinfunction "B2_6") (pintype "bidirectional"))
      (node (ref "R35") (pin "2") (pinfunction "2_2") (pintype "passive"))
    )
    (net (code "152") (name "PWM_MC3") (class "Default")
      (node (ref "IC2") (pin "7") (pinfunction "B1_7") (pintype "bidirectional"))
      (node (ref "R37") (pin "2") (pinfunction "2_2") (pintype "passive"))
    )
    (net (code "153") (name "PWM_MC4") (class "Default")
      (node (ref "IC2") (pin "6") (pinfunction "B2_6") (pintype "bidirectional"))
      (node (ref "R38") (pin "2") (pinfunction "2_2") (pintype "passive"))
    )
    (net (code "154") (name "RESET#") (class "Default")
      (node (ref "C20") (pin "1") (pinfunction "1_1") (pintype "passive"))
      (node (ref "D5") (pin "2") (pinfunction "A_2") (pintype "passive"))
      (node (ref "R1") (pin "1") (pinfunction "1_1") (pintype "passive"))
      (node (ref "SW1") (pin "P") (pinfunction "P_P") (pintype "passive"))
      (node (ref "SW1") (pin "P1") (pinfunction "P_P1") (pintype "passive"))
      (node (ref "XMC4500") (pin "65") (pinfunction "PORST#_65") (pintype "bidirectional"))
    )
    (net (code "155") (name "RTC1") (class "Default")
      (node (ref "XMC4500") (pin "15") (pinfunction "RTC_XTAL_1_15") (pintype "bidirectional"))
    )
    (net (code "156") (name "RTC2") (class "Default")
      (node (ref "XMC4500") (pin "16") (pinfunction "RTC_XTAL_2_16") (pintype "bidirectional"))
    )
    (net (code "157") (name "SWV") (class "Default")
      (node (ref "CON2") (pin "6") (pinfunction "6_6") (pintype "passive"))
      (node (ref "SJ1") (pin "2") (pinfunction "2_2") (pintype "passive"))
      (node (ref "XMC4500") (pin "51") (pinfunction "P2.1_51") (pintype "bidirectional"))
    )
    (net (code "158") (name "SWV_DBG") (class "Default")
      (node (ref "SJ1") (pin "1") (pinfunction "1_1") (pintype "passive"))
      (node (ref "XMC4200") (pin "2") (pinfunction "P0.0_2") (pintype "bidirectional"))
      (node (ref "XMC4200") (pin "24") (pinfunction "P2.2_24") (pintype "bidirectional"))
    )
    (net (code "159") (name "TCK") (class "Default")
      (node (ref "CON2") (pin "4") (pinfunction "4_4") (pintype "passive"))
      (node (ref "XMC4200") (pin "22") (pinfunction "P2.4_22") (pintype "bidirectional"))
      (node (ref "XMC4200") (pin "39") (pinfunction "P1.1_39") (pintype "bidirectional"))
      (node (ref "XMC4500") (pin "67") (pinfunction "TCK_67") (pintype "bidirectional"))
    )
    (net (code "160") (name "TMS") (class "Default")
      (node (ref "CON2") (pin "2") (pinfunction "2_2") (pintype "passive"))
      (node (ref "XMC4200") (pin "35") (pinfunction "P1.5_35") (pintype "bidirectional"))
      (node (ref "XMC4200") (pin "36") (pinfunction "P1.4_36") (pintype "bidirectional"))
      (node (ref "XMC4500") (pin "66") (pinfunction "TMS_66") (pintype "bidirectional"))
    )
    (net (code "161") (name "USB_D+") (class "Default")
      (node (ref "R11") (pin "2") (pinfunction "2_2") (pintype "passive"))
      (node (ref "XMC4500") (pin "9") (pinfunction "USB_D+_9") (pintype "bidirectional"))
    )
    (net (code "162") (name "USB_D-") (class "Default")
      (node (ref "R10") (pin "2") (pinfunction "2_2") (pintype "passive"))
      (node (ref "XMC4500") (pin "8") (pinfunction "USB_D-_8") (pintype "bidirectional"))
    )
    (net (code "163") (name "VAREF") (class "Default")
      (node (ref "C16") (pin "1") (pinfunction "1_1") (pintype "passive"))
      (node (ref "L2") (pin "1") (pinfunction "1_1") (pintype "passive"))
      (node (ref "XMC4500") (pin "33") (pinfunction "VAREF_33") (pintype "bidirectional"))
    )
    (net (code "164") (name "VBAT_IN") (class "Default")
      (node (ref "C25") (pin "1") (pinfunction "1_1") (pintype "passive"))
      (node (ref "C27") (pin "1") (pinfunction "1_1") (pintype "passive"))
      (node (ref "C32") (pin "1") (pinfunction "1_1") (pintype "passive"))
      (node (ref "C33") (pin "2") (pinfunction "2_2") (pintype "passive"))
      (node (ref "CON9") (pin "2") (pinfunction "2_2") (pintype "passive"))
      (node (ref "CON9") (pin "4") (pinfunction "4_4") (pintype "passive"))
      (node (ref "EL1") (pin "1") (pinfunction "1_1") (pintype "passive"))
      (node (ref "EL2") (pin "1") (pinfunction "1_1") (pintype "passive"))
      (node (ref "EL3") (pin "1") (pinfunction "1_1") (pintype "passive"))
      (node (ref "EL4") (pin "1") (pinfunction "1_1") (pintype "passive"))
      (node (ref "L4") (pin "P$2") (pinfunction "2_P$2") (pintype "bidirectional"))
      (node (ref "M1_OUT") (pin "10") (pinfunction "10_10") (pintype "passive"))
      (node (ref "M1_OUT") (pin "9") (pinfunction "9_9") (pintype "passive"))
      (node (ref "M2_OUT") (pin "10") (pinfunction "10_10") (pintype "passive"))
      (node (ref "M2_OUT") (pin "9") (pinfunction "9_9") (pintype "passive"))
      (node (ref "M3_OUT") (pin "10") (pinfunction "10_10") (pintype "passive"))
      (node (ref "M3_OUT") (pin "9") (pinfunction "9_9") (pintype "passive"))
      (node (ref "M4_OUT") (pin "10") (pinfunction "10_10") (pintype "passive"))
      (node (ref "M4_OUT") (pin "9") (pinfunction "9_9") (pintype "passive"))
      (node (ref "PAD1") (pin "P$1") (pinfunction "P$1_P$1") (pintype "bidirectional"))
      (node (ref "VREG1") (pin "7") (pinfunction "7_7") (pintype "bidirectional"))
    )
    (net (code "165") (name "VBUS") (class "Default")
      (node (ref "D2") (pin "A") (pinfunction "A_A") (pintype "passive"))
      (node (ref "L1") (pin "1") (pinfunction "1_1") (pintype "passive"))
      (node (ref "XMC4500") (pin "10") (pinfunction "VBUS_10") (pintype "bidirectional"))
    )
    (net (code "166") (name "VDD3.3") (class "Default")
      (node (ref "C1") (pin "1") (pinfunction "1_1") (pintype "passive"))
      (node (ref "C14") (pin "1") (pinfunction "1_1") (pintype "passive"))
      (node (ref "C15") (pin "2") (pinfunction "2_2") (pintype "passive"))
      (node (ref "C18") (pin "2") (pinfunction "2_2") (pintype "passive"))
      (node (ref "C2") (pin "1") (pinfunction "1_1") (pintype "passive"))
      (node (ref "C204") (pin "1") (pinfunction "1_1") (pintype "passive"))
      (node (ref "C21") (pin "2") (pinfunction "2_2") (pintype "passive"))
      (node (ref "C211") (pin "1") (pinfunction "1_1") (pintype "passive"))
      (node (ref "C212") (pin "1") (pinfunction "1_1") (pintype "passive"))
      (node (ref "C213") (pin "1") (pinfunction "1_1") (pintype "passive"))
      (node (ref "C23") (pin "1") (pinfunction "1_1") (pintype "passive"))
      (node (ref "C3") (pin "1") (pinfunction "1_1") (pintype "passive"))
      (node (ref "C37") (pin "1") (pinfunction "1_1") (pintype "passive"))
      (node (ref "C38") (pin "1") (pinfunction "1_1") (pintype "passive"))
      (node (ref "C39") (pin "1") (pinfunction "1_1") (pintype "passive"))
      (node (ref "C4") (pin "1") (pinfunction "1_1") (pintype "passive"))
      (node (ref "C42") (pin "1") (pinfunction "1_1") (pintype "passive"))
      (node (ref "C43") (pin "1") (pinfunction "1_1") (pintype "passive"))
      (node (ref "C5") (pin "1") (pinfunction "1_1") (pintype "passive"))
      (node (ref "C6") (pin "1") (pinfunction "1_1") (pintype "passive"))
      (node (ref "CON10") (pin "3") (pinfunction "3_3") (pintype "passive"))
      (node (ref "CON12") (pin "1") (pinfunction "1_1") (pintype "passive"))
      (node (ref "CON15") (pin "1") (pinfunction "1_1") (pintype "passive"))
      (node (ref "CON2") (pin "1") (pinfunction "1_1") (pintype "passive"))
      (node (ref "CON3") (pin "2") (pinfunction "2_2") (pintype "passive"))
      (node (ref "CON4") (pin "1") (pinfunction "1_1") (pintype "passive"))
      (node (ref "D3") (pin "P$2") (pinfunction "P$2_P$2") (pintype "bidirectional"))
      (node (ref "DPS310") (pin "P6") (pinfunction "VDDIO_P6") (pintype "bidirectional"))
      (node (ref "DPS310") (pin "P8") (pinfunction "VDD_P8") (pintype "bidirectional"))
      (node (ref "IC1") (pin "1") (pinfunction "VCCA_1") (pintype "bidirectional"))
      (node (ref "IC1") (pin "5") (pinfunction "DIR_5") (pintype "bidirectional"))
      (node (ref "IC2") (pin "1") (pinfunction "VCCA_1") (pintype "bidirectional"))
      (node (ref "IC2") (pin "5") (pinfunction "DIR_5") (pintype "bidirectional"))
      (node (ref "L2") (pin "2") (pinfunction "2_2") (pintype "passive"))
      (node (ref "L3") (pin "2") (pinfunction "2_2") (pintype "passive"))
      (node (ref "M1_IN") (pin "3") (pinfunction "3_3") (pintype "passive"))
      (node (ref "M1_IN") (pin "4") (pinfunction "4_4") (pintype "passive"))
      (node (ref "M2_IN") (pin "3") (pinfunction "3_3") (pintype "passive"))
      (node (ref "M2_IN") (pin "4") (pinfunction "4_4") (pintype "passive"))
      (node (ref "M3_IN") (pin "3") (pinfunction "3_3") (pintype "passive"))
      (node (ref "M3_IN") (pin "4") (pinfunction "4_4") (pintype "passive"))
      (node (ref "M4_IN") (pin "3") (pinfunction "3_3") (pintype "passive"))
      (node (ref "M4_IN") (pin "4") (pinfunction "4_4") (pintype "passive"))
      (node (ref "MPU9250") (pin "1") (pinfunction "1_1") (pintype "bidirectional"))
      (node (ref "MPU9250") (pin "13") (pinfunction "13_13") (pintype "bidirectional"))
      (node (ref "MPU9250") (pin "22") (pinfunction "22_22") (pintype "bidirectional"))
      (node (ref "MPU9250") (pin "8") (pinfunction "8_8") (pintype "bidirectional"))
      (node (ref "MPU9250") (pin "9") (pinfunction "9_9") (pintype "bidirectional"))
      (node (ref "R1") (pin "2") (pinfunction "2_2") (pintype "passive"))
      (node (ref "R14") (pin "2") (pinfunction "2_2") (pintype "passive"))
      (node (ref "R15") (pin "2") (pinfunction "2_2") (pintype "passive"))
      (node (ref "R16") (pin "1") (pinfunction "1_1") (pintype "passive"))
      (node (ref "R17") (pin "1") (pinfunction "1_1") (pintype "passive"))
      (node (ref "R2") (pin "1") (pinfunction "1_1") (pintype "passive"))
      (node (ref "R201") (pin "1") (pinfunction "1_1") (pintype "passive"))
      (node (ref "R202") (pin "1") (pinfunction "1_1") (pintype "passive"))
      (node (ref "R211") (pin "2") (pinfunction "2_2") (pintype "passive"))
      (node (ref "R4") (pin "1") (pinfunction "1_1") (pintype "passive"))
      (node (ref "R5") (pin "2") (pinfunction "2_2") (pintype "passive"))
      (node (ref "R8") (pin "1") (pinfunction "1_1") (pintype "passive"))
      (node (ref "R9") (pin "1") (pinfunction "1_1") (pintype "passive"))
      (node (ref "RN42") (pin "VDD") (pinfunction "11_VDD_VDD") (pintype "bidirectional"))
      (node (ref "U$9") (pin "P$1") (pinfunction "P$1_P$1") (pintype "bidirectional"))
      (node (ref "VREG2") (pin "2") (pinfunction "OUT1_2") (pintype "power_in"))
      (node (ref "VREG2") (pin "4") (pinfunction "OUT2_4") (pintype "power_in"))
      (node (ref "XMC4200") (pin "10") (pinfunction "VBAT_10") (pintype "bidirectional"))
      (node (ref "XMC4200") (pin "18") (pinfunction "VAREF_18") (pintype "bidirectional"))
      (node (ref "XMC4200") (pin "28") (pinfunction "VDDP1_28") (pintype "bidirectional"))
      (node (ref "XMC4200") (pin "41") (pinfunction "VDDP2_41") (pintype "bidirectional"))
      (node (ref "XMC4200") (pin "5") (pinfunction "VDDP_5") (pintype "bidirectional"))
      (node (ref "XMC4500") (pin "11") (pinfunction "VDDP_11") (pintype "bidirectional"))
      (node (ref "XMC4500") (pin "17") (pinfunction "VBAT_17") (pintype "bidirectional"))
      (node (ref "XMC4500") (pin "43") (pinfunction "VDDP1_43") (pintype "bidirectional"))
      (node (ref "XMC4500") (pin "60") (pinfunction "VDDP2_60") (pintype "bidirectional"))
      (node (ref "XMC4500") (pin "87") (pinfunction "VDDP3_87") (pintype "bidirectional"))
    )
    (net (code "167") (name "VDD5") (class "Default")
      (node (ref "C22") (pin "1") (pinfunction "1_1") (pintype "passive"))
      (node (ref "C26") (pin "1") (pinfunction "1_1") (pintype "passive"))
      (node (ref "C35") (pin "1") (pinfunction "1_1") (pintype "passive"))
      (node (ref "C40") (pin "1") (pinfunction "1_1") (pintype "passive"))
      (node (ref "C41") (pin "1") (pinfunction "1_1") (pintype "passive"))
      (node (ref "CON14") (pin "1") (pinfunction "1_1") (pintype "passive"))
      (node (ref "D2") (pin "C") (pinfunction "C_C") (pintype "passive"))
      (node (ref "IC1") (pin "8") (pinfunction "VCCB_8") (pintype "bidirectional"))
      (node (ref "IC2") (pin "8") (pinfunction "VCCB_8") (pintype "bidirectional"))
      (node (ref "L5") (pin "P$2") (pinfunction "2_P$2") (pintype "bidirectional"))
      (node (ref "V203") (pin "C") (pinfunction "C_C") (pintype "passive"))
      (node (ref "VREG1") (pin "4") (pinfunction "4_4") (pintype "bidirectional"))
      (node (ref "VREG2") (pin "3") (pinfunction "IN_3") (pintype "power_in"))
    )
    (net (code "168") (name "VDDA") (class "Default")
      (node (ref "C17") (pin "1") (pinfunction "1_1") (pintype "passive"))
      (node (ref "L3") (pin "1") (pinfunction "1_1") (pintype "passive"))
      (node (ref "XMC4500") (pin "35") (pinfunction "VDDA_35") (pintype "bidirectional"))
    )
    (net (code "169") (name "VDDC") (class "Default")
      (node (ref "C10") (pin "1") (pinfunction "1_1") (pintype "passive"))
      (node (ref "C11") (pin "1") (pinfunction "1_1") (pintype "passive"))
      (node (ref "C7") (pin "1") (pinfunction "1_1") (pintype "passive"))
      (node (ref "C8") (pin "1") (pinfunction "1_1") (pintype "passive"))
      (node (ref "C9") (pin "1") (pinfunction "1_1") (pintype "passive"))
      (node (ref "XMC4500") (pin "12") (pinfunction "VDDC_12") (pintype "bidirectional"))
      (node (ref "XMC4500") (pin "42") (pinfunction "VDDC1_42") (pintype "bidirectional"))
      (node (ref "XMC4500") (pin "64") (pinfunction "VDDC2_64") (pintype "bidirectional"))
      (node (ref "XMC4500") (pin "86") (pinfunction "VDDC3_86") (pintype "bidirectional"))
    )
    (net (code "170") (name "WTCK") (class "Default")
      (node (ref "U$9") (pin "P$2") (pinfunction "P$2_P$2") (pintype "bidirectional"))
      (node (ref "XMC4200") (pin "34") (pinfunction "TCK_34") (pintype "bidirectional"))
    )
    (net (code "171") (name "WTMS") (class "Default")
      (node (ref "U$9") (pin "P$3") (pinfunction "P$3_P$3") (pintype "bidirectional"))
      (node (ref "XMC4200") (pin "33") (pinfunction "TMS_33") (pintype "bidirectional"))
    )
    (net (code "172") (name "unconnected-(CON2-Pad7)") (class "Default")
      (node (ref "CON2") (pin "7") (pinfunction "7_7") (pintype "passive"))
    )
    (net (code "173") (name "unconnected-(DPS310-CSB-PadP2)") (class "Default")
      (node (ref "DPS310") (pin "P2") (pinfunction "CSB_P2") (pintype "bidirectional"))
    )
    (net (code "174") (name "unconnected-(MPU9250-Pad2)") (class "Default")
      (node (ref "MPU9250") (pin "2") (pinfunction "2_2") (pintype "bidirectional"))
    )
    (net (code "175") (name "unconnected-(MPU9250-Pad3)") (class "Default")
      (node (ref "MPU9250") (pin "3") (pinfunction "3_3") (pintype "bidirectional"))
    )
    (net (code "176") (name "unconnected-(MPU9250-Pad4)") (class "Default")
      (node (ref "MPU9250") (pin "4") (pinfunction "4_4") (pintype "bidirectional"))
    )
    (net (code "177") (name "unconnected-(MPU9250-Pad5)") (class "Default")
      (node (ref "MPU9250") (pin "5") (pinfunction "5_5") (pintype "bidirectional"))
    )
    (net (code "178") (name "unconnected-(MPU9250-Pad6)") (class "Default")
      (node (ref "MPU9250") (pin "6") (pinfunction "6_6") (pintype "bidirectional"))
    )
    (net (code "179") (name "unconnected-(MPU9250-Pad7)") (class "Default")
      (node (ref "MPU9250") (pin "7") (pinfunction "7_7") (pintype "bidirectional"))
    )
    (net (code "180") (name "unconnected-(MPU9250-Pad14)") (class "Default")
      (node (ref "MPU9250") (pin "14") (pinfunction "14_14") (pintype "bidirectional"))
    )
    (net (code "181") (name "unconnected-(MPU9250-Pad15)") (class "Default")
      (node (ref "MPU9250") (pin "15") (pinfunction "15_15") (pintype "bidirectional"))
    )
    (net (code "182") (name "unconnected-(MPU9250-Pad16)") (class "Default")
      (node (ref "MPU9250") (pin "16") (pinfunction "16_16") (pintype "bidirectional"))
    )
    (net (code "183") (name "unconnected-(MPU9250-Pad17)") (class "Default")
      (node (ref "MPU9250") (pin "17") (pinfunction "17_17") (pintype "bidirectional"))
    )
    (net (code "184") (name "unconnected-(MPU9250-Pad19)") (class "Default")
      (node (ref "MPU9250") (pin "19") (pinfunction "19_19") (pintype "bidirectional"))
    )
    (net (code "185") (name "unconnected-(MPU9250-Pad21)") (class "Default")
      (node (ref "MPU9250") (pin "21") (pinfunction "21_21") (pintype "bidirectional"))
    )
    (net (code "186") (name "unconnected-(USB-PGH1-PadP$1)") (class "Default")
      (node (ref "USB") (pin "P$1") (pinfunction "PGH1_P$1") (pintype "bidirectional"))
    )
    (net (code "187") (name "unconnected-(USB-PGH2-PadP$2)") (class "Default")
      (node (ref "USB") (pin "P$2") (pinfunction "PGH2_P$2") (pintype "bidirectional"))
    )
    (net (code "188") (name "unconnected-(USB-PGH3-PadP$3)") (class "Default")
      (node (ref "USB") (pin "P$3") (pinfunction "PGH3_P$3") (pintype "bidirectional"))
    )
    (net (code "189") (name "unconnected-(USB-PGH4-PadP$4)") (class "Default")
      (node (ref "USB") (pin "P$4") (pinfunction "PGH4_P$4") (pintype "bidirectional"))
    )
    (net (code "190") (name "unconnected-(USB-Pad2)") (class "Default")
      (node (ref "USB") (pin "2") (pinfunction "2_2") (pintype "passive"))
    )
    (net (code "191") (name "unconnected-(USB1-PGH1-PadP$1)") (class "Default")
      (node (ref "USB1") (pin "P$1") (pinfunction "PGH1_P$1") (pintype "bidirectional"))
    )
    (net (code "192") (name "unconnected-(USB1-PGH2-PadP$2)") (class "Default")
      (node (ref "USB1") (pin "P$2") (pinfunction "PGH2_P$2") (pintype "bidirectional"))
    )
    (net (code "193") (name "unconnected-(USB1-PGH3-PadP$3)") (class "Default")
      (node (ref "USB1") (pin "P$3") (pinfunction "PGH3_P$3") (pintype "bidirectional"))
    )
    (net (code "194") (name "unconnected-(USB1-PGH4-PadP$4)") (class "Default")
      (node (ref "USB1") (pin "P$4") (pinfunction "PGH4_P$4") (pintype "bidirectional"))
    )
    (net (code "195") (name "unconnected-(USB1-Pad2)") (class "Default")
      (node (ref "USB1") (pin "2") (pinfunction "2_2") (pintype "passive"))
    )
    (net (code "196") (name "unconnected-(XMC4200-P0.3-Pad47)") (class "Default")
      (node (ref "XMC4200") (pin "47") (pinfunction "P0.3_47") (pintype "bidirectional"))
    )
    (net (code "197") (name "unconnected-(XMC4200-P0.6-Pad44)") (class "Default")
      (node (ref "XMC4200") (pin "44") (pinfunction "P0.6_44") (pintype "bidirectional"))
    )
    (net (code "198") (name "unconnected-(XMC4200-P0.7-Pad43)") (class "Default")
      (node (ref "XMC4200") (pin "43") (pinfunction "P0.7_43") (pintype "bidirectional"))
    )
    (net (code "199") (name "unconnected-(XMC4200-P0.8-Pad42)") (class "Default")
      (node (ref "XMC4200") (pin "42") (pinfunction "P0.8_42") (pintype "bidirectional"))
    )
    (net (code "200") (name "unconnected-(XMC4200-P1.2-Pad38)") (class "Default")
      (node (ref "XMC4200") (pin "38") (pinfunction "P1.2_38") (pintype "bidirectional"))
    )
    (net (code "201") (name "unconnected-(XMC4200-P1.3-Pad37)") (class "Default")
      (node (ref "XMC4200") (pin "37") (pinfunction "P1.3_37") (pintype "bidirectional"))
    )
    (net (code "202") (name "unconnected-(XMC4200-P2.0-Pad26)") (class "Default")
      (node (ref "XMC4200") (pin "26") (pinfunction "P2.0_26") (pintype "bidirectional"))
    )
    (net (code "203") (name "unconnected-(XMC4200-P2.1-Pad25)") (class "Default")
      (node (ref "XMC4200") (pin "25") (pinfunction "P2.1_25") (pintype "bidirectional"))
    )
    (net (code "204") (name "unconnected-(XMC4200-P2.5-Pad21)") (class "Default")
      (node (ref "XMC4200") (pin "21") (pinfunction "P2.5_21") (pintype "bidirectional"))
    )
    (net (code "205") (name "unconnected-(XMC4200-P14.0-Pad16)") (class "Default")
      (node (ref "XMC4200") (pin "16") (pinfunction "P14.0_16") (pintype "bidirectional"))
    )
    (net (code "206") (name "unconnected-(XMC4200-P14.3-Pad15)") (class "Default")
      (node (ref "XMC4200") (pin "15") (pinfunction "P14.3_15") (pintype "bidirectional"))
    )
    (net (code "207") (name "unconnected-(XMC4200-P14.9-Pad19)") (class "Default")
      (node (ref "XMC4200") (pin "19") (pinfunction "P14.9_19") (pintype "bidirectional"))
    )
    (net (code "208") (name "unconnected-(XMC4200-RTC_XTAL_1-Pad8)") (class "Default")
      (node (ref "XMC4200") (pin "8") (pinfunction "RTC_XTAL_1_8") (pintype "bidirectional"))
    )
    (net (code "209") (name "unconnected-(XMC4200-RTC_XTAL_2-Pad9)") (class "Default")
      (node (ref "XMC4200") (pin "9") (pinfunction "RTC_XTAL_2_9") (pintype "bidirectional"))
    )
  )
)
